# USB_Hub_Switch.net
KiCad netlist of a schematic drawn in EasyEDA Pro
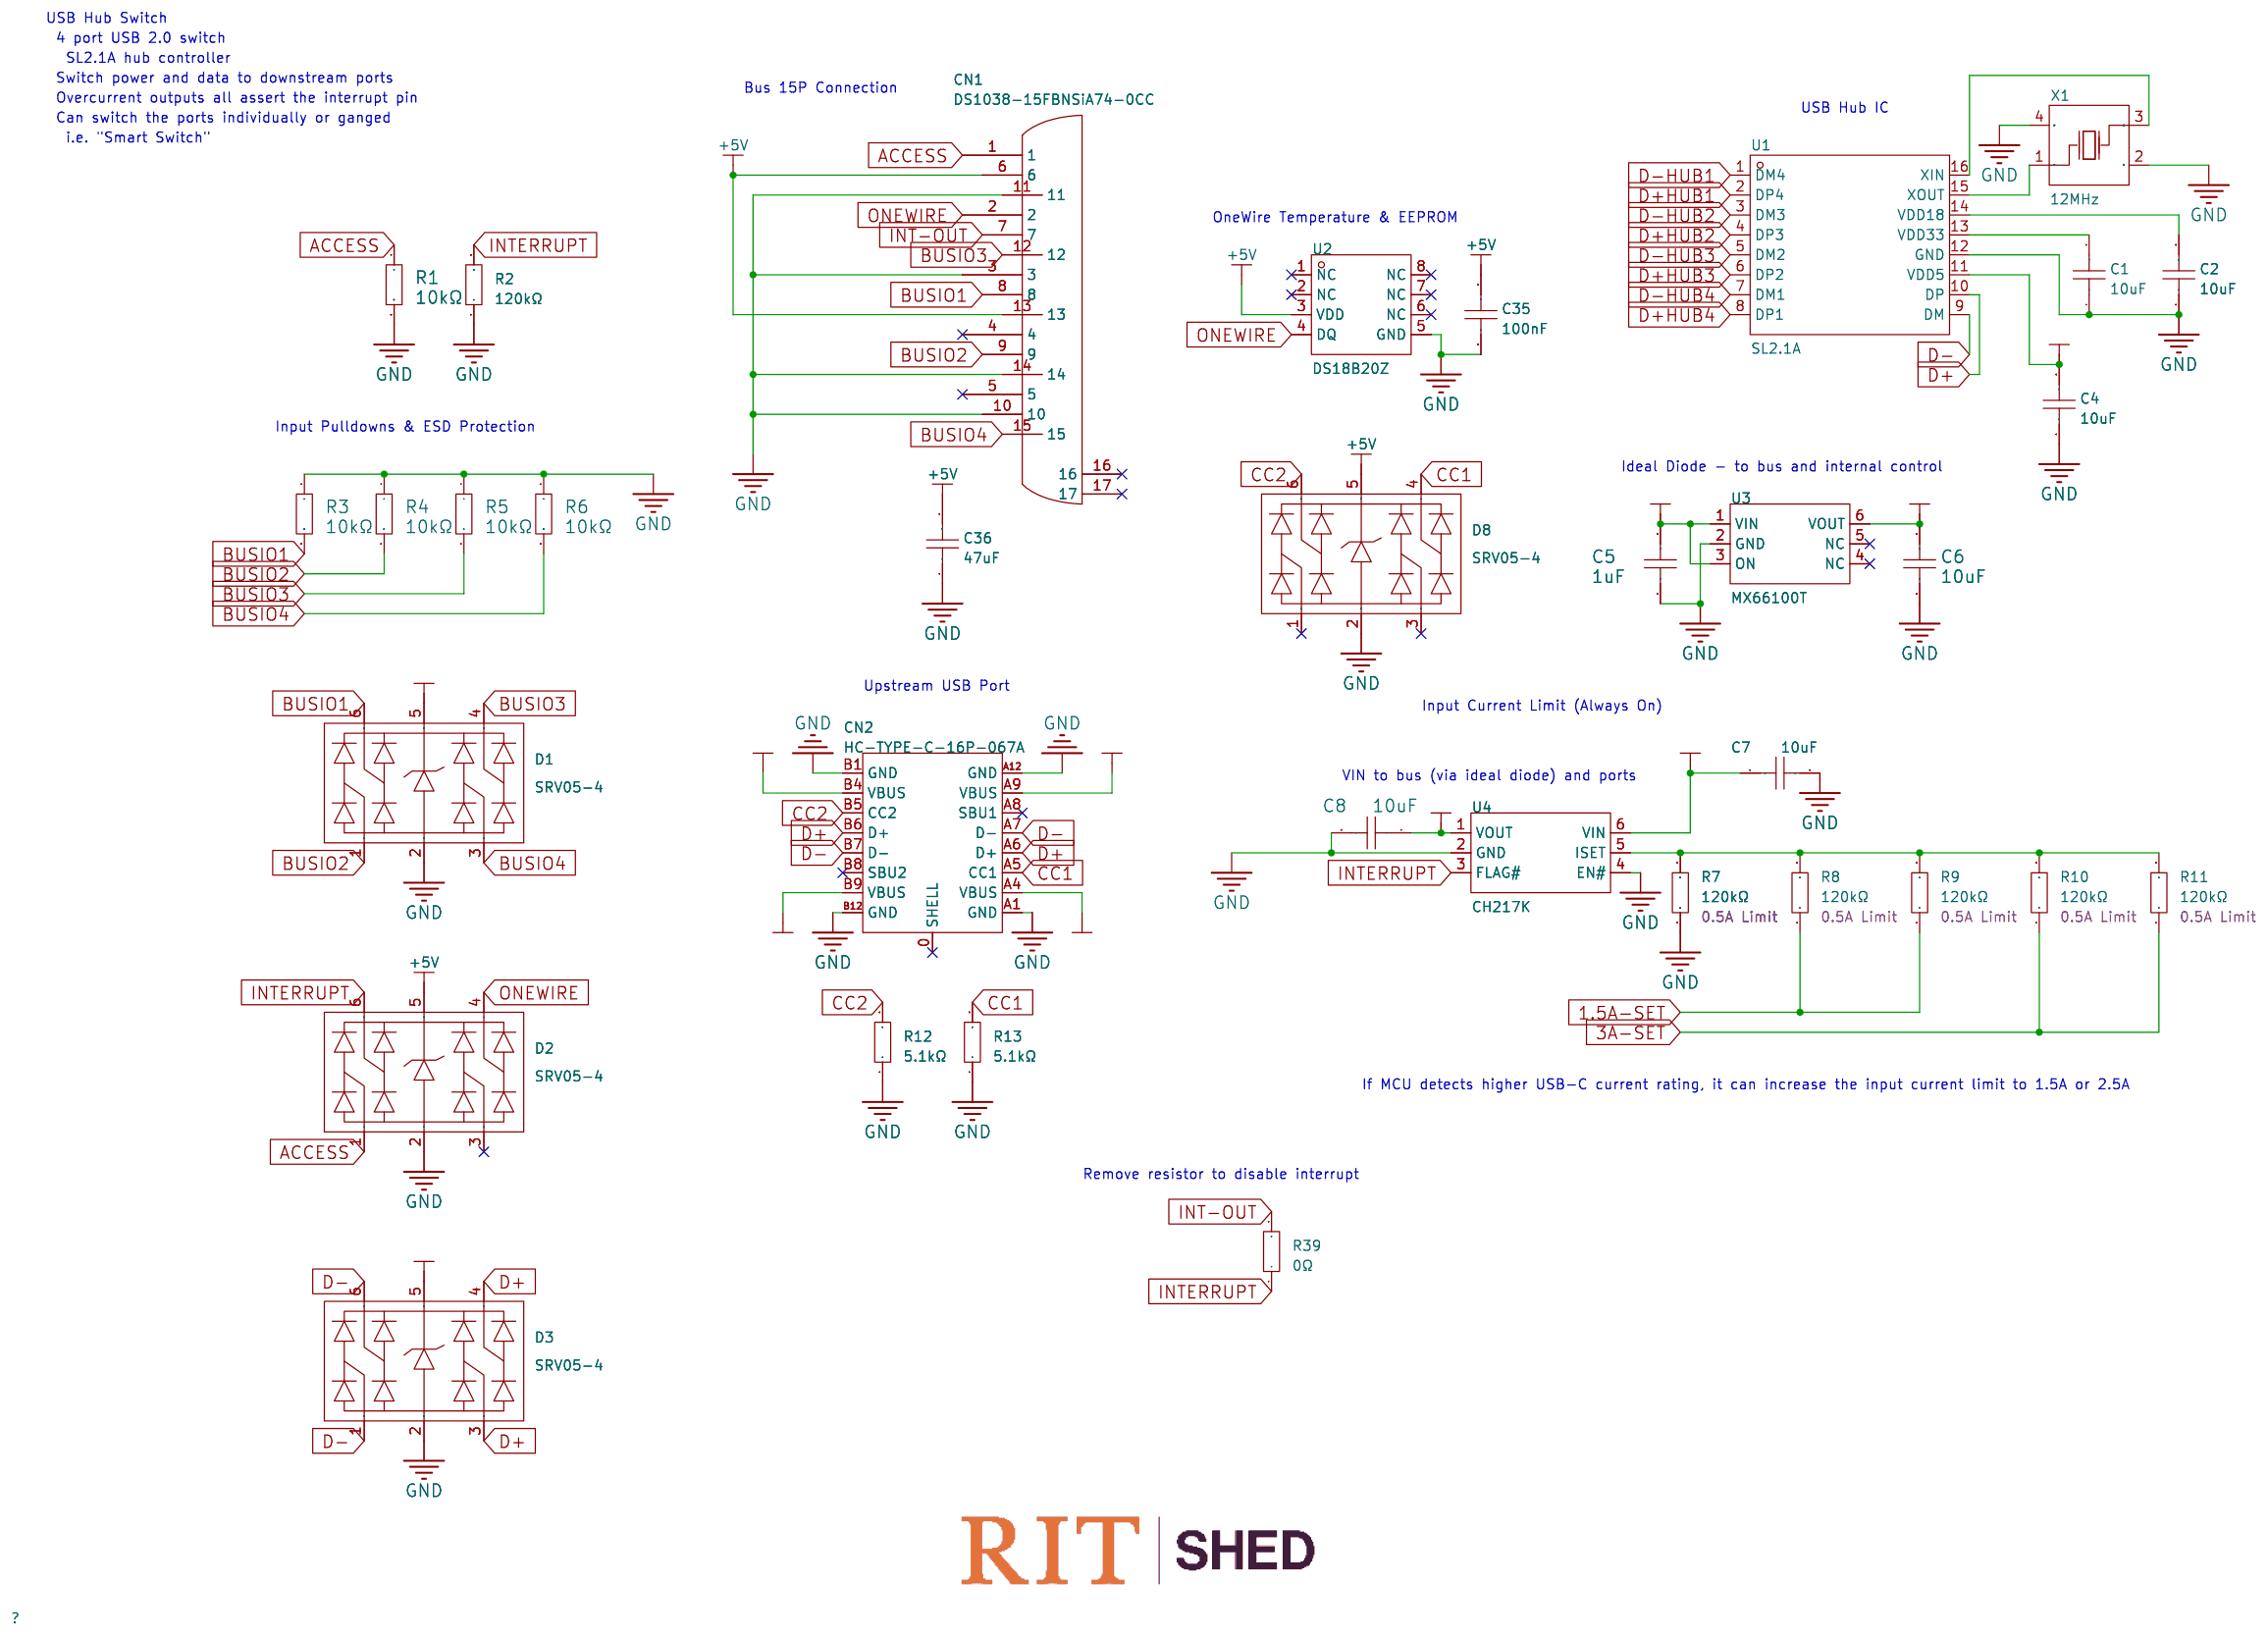
[diagram p0: Upstream Ports]
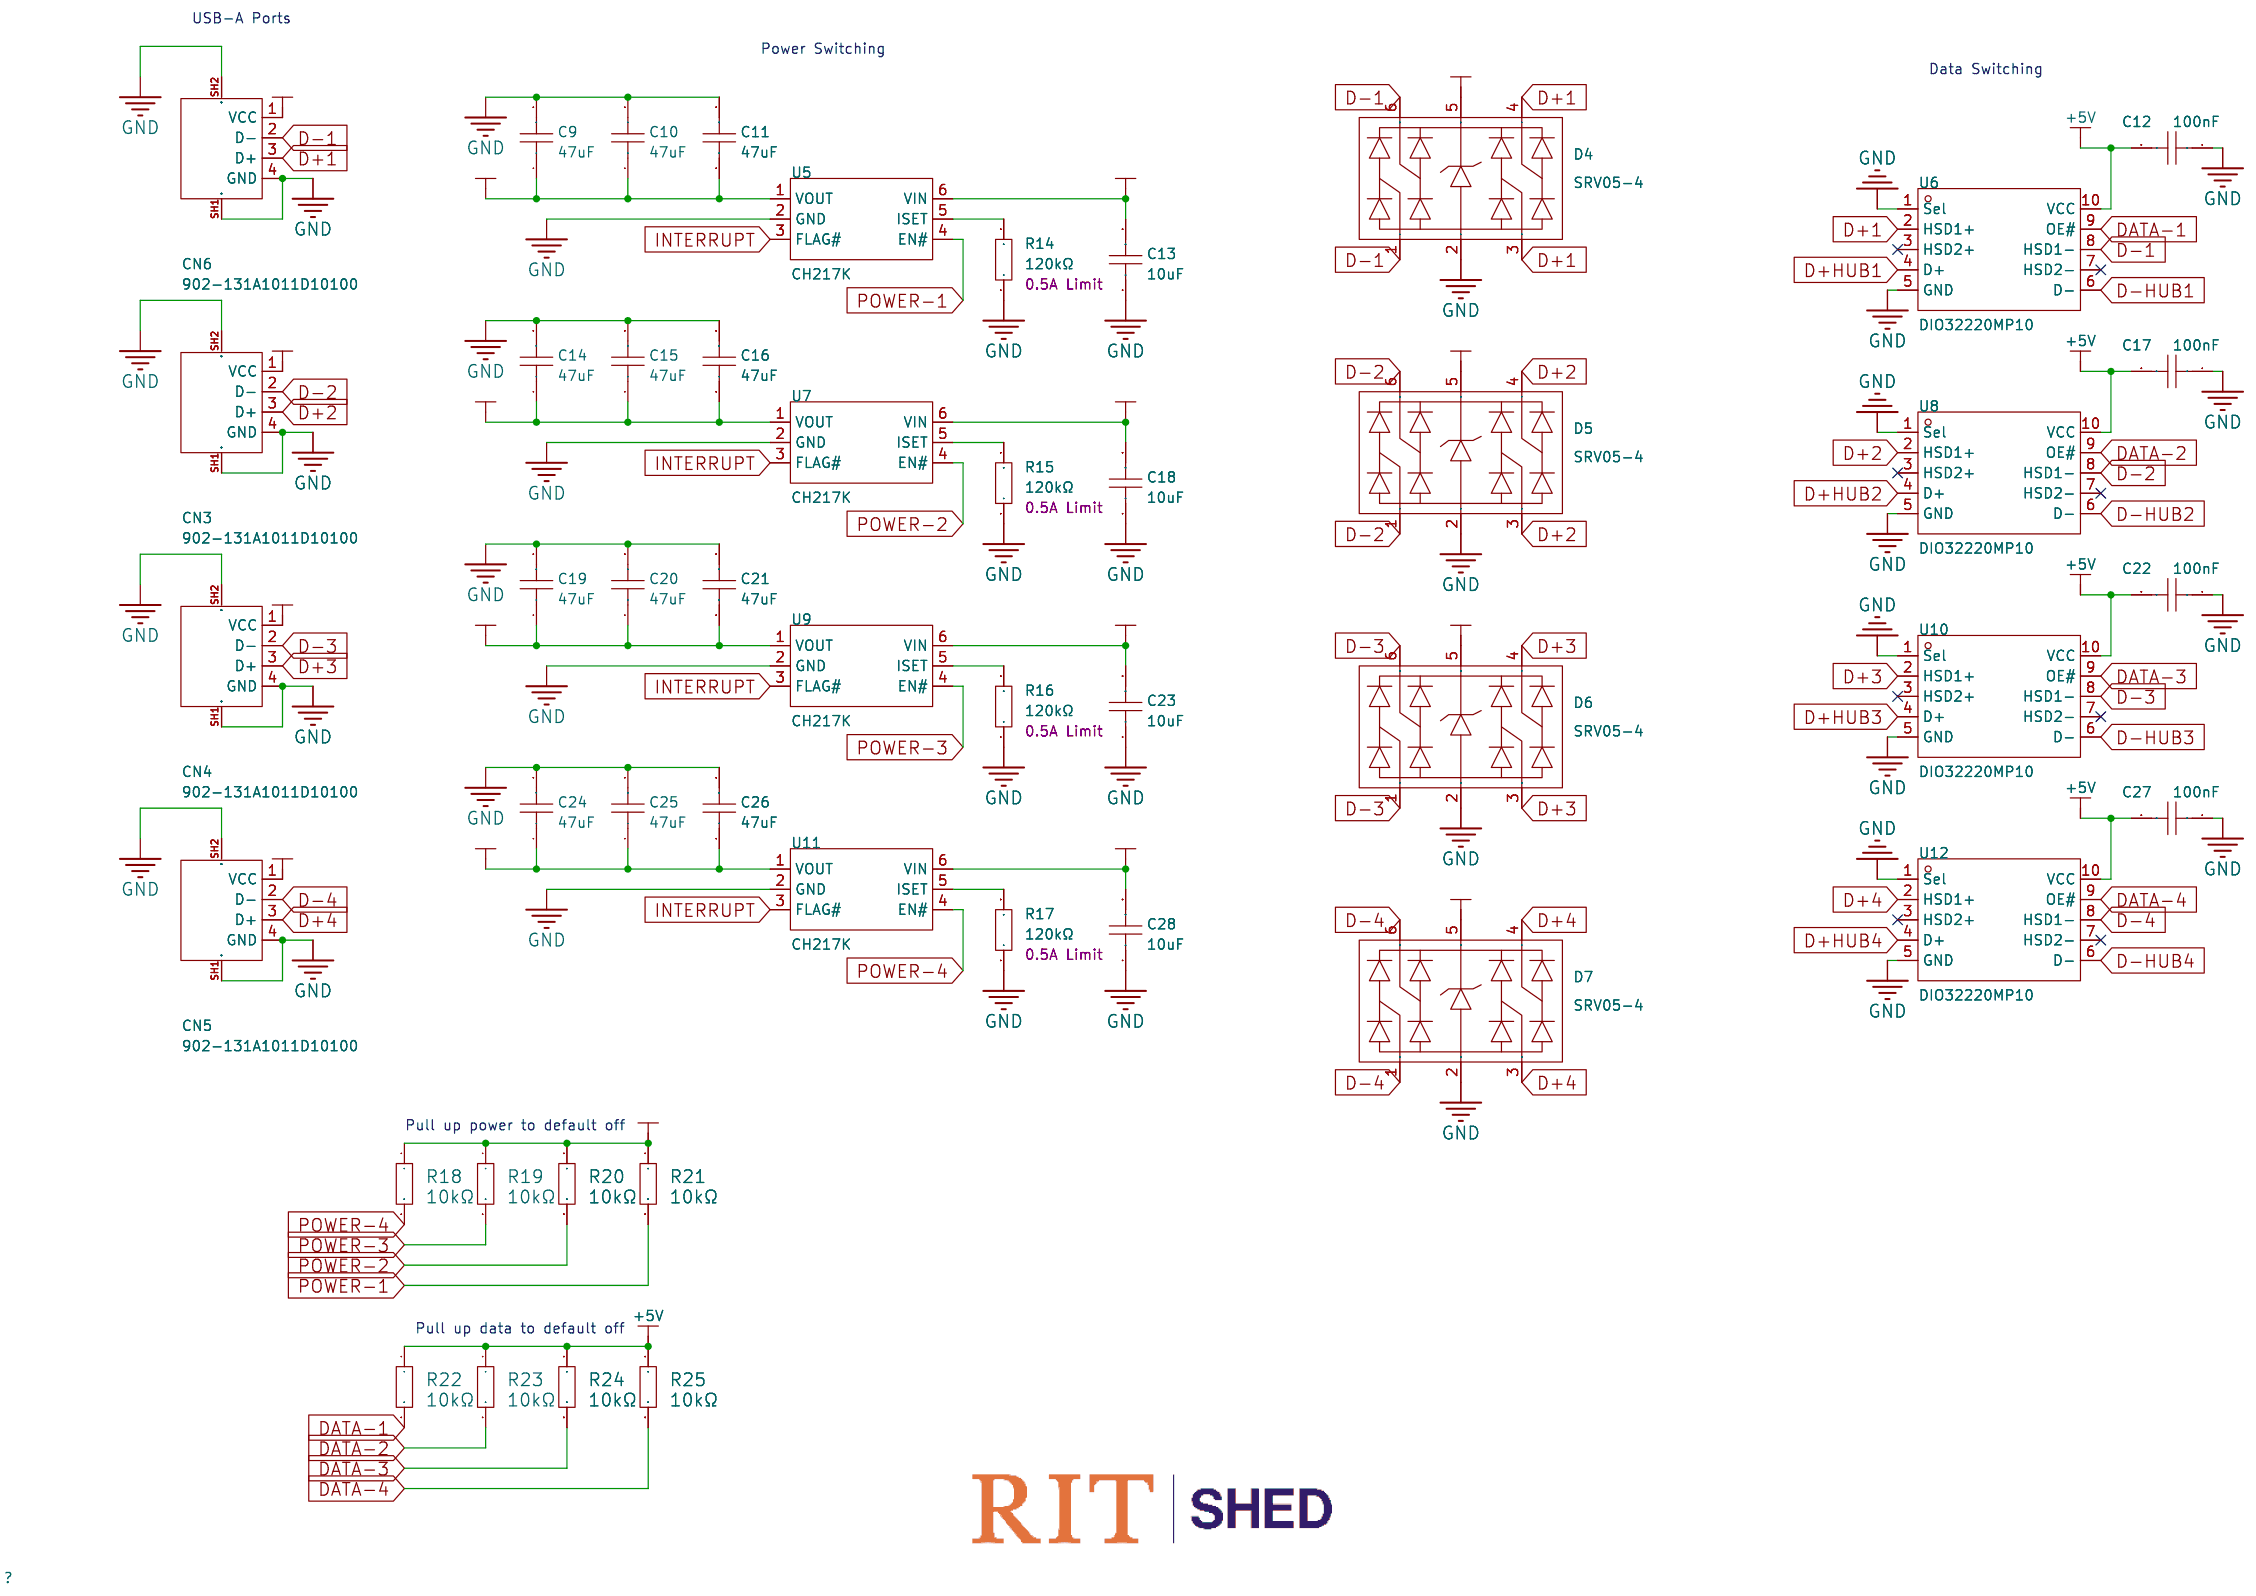
[diagram p1: Downstream Ports]
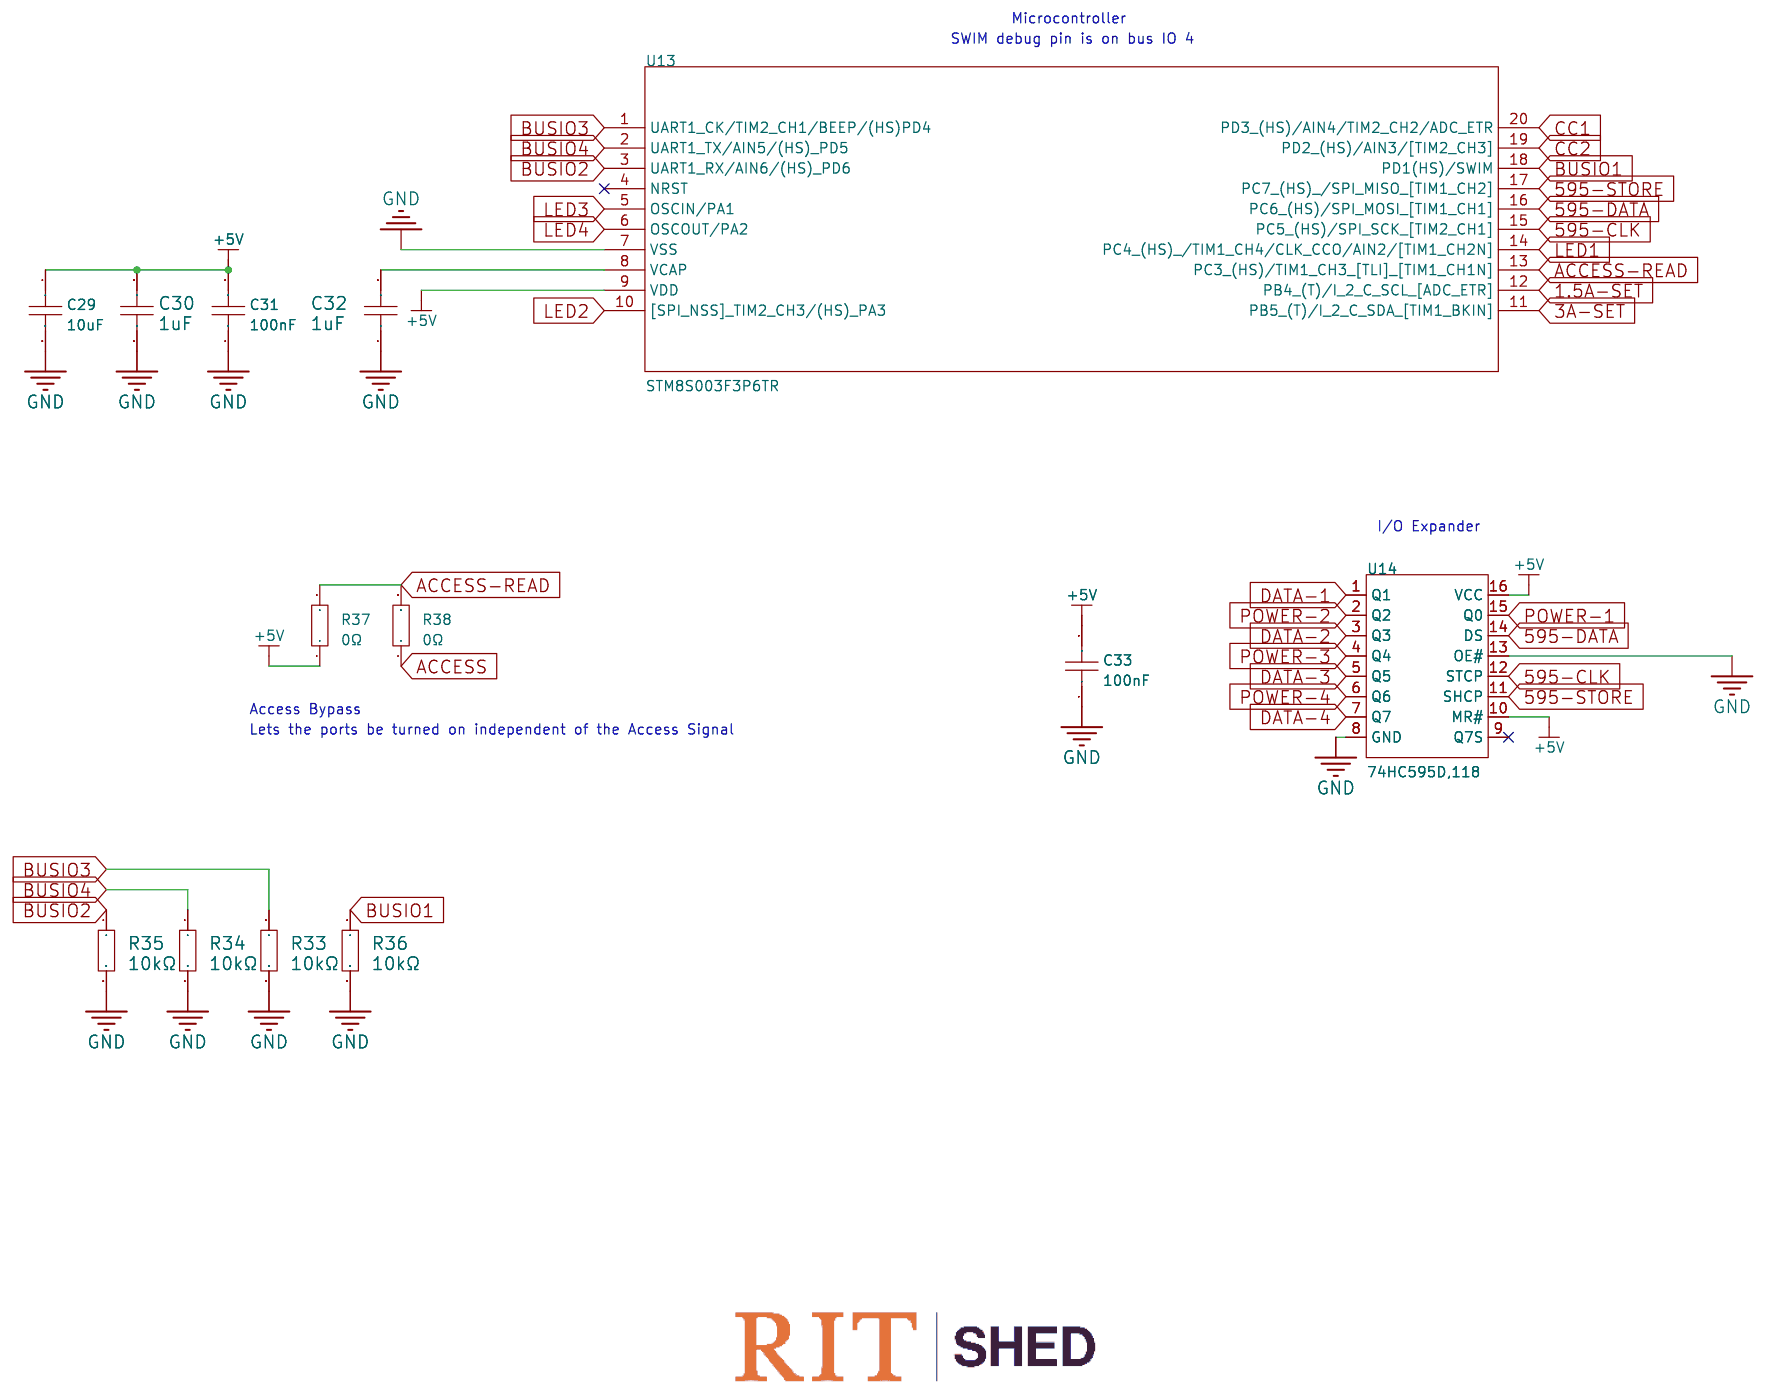
[diagram p2: Microcontroller]
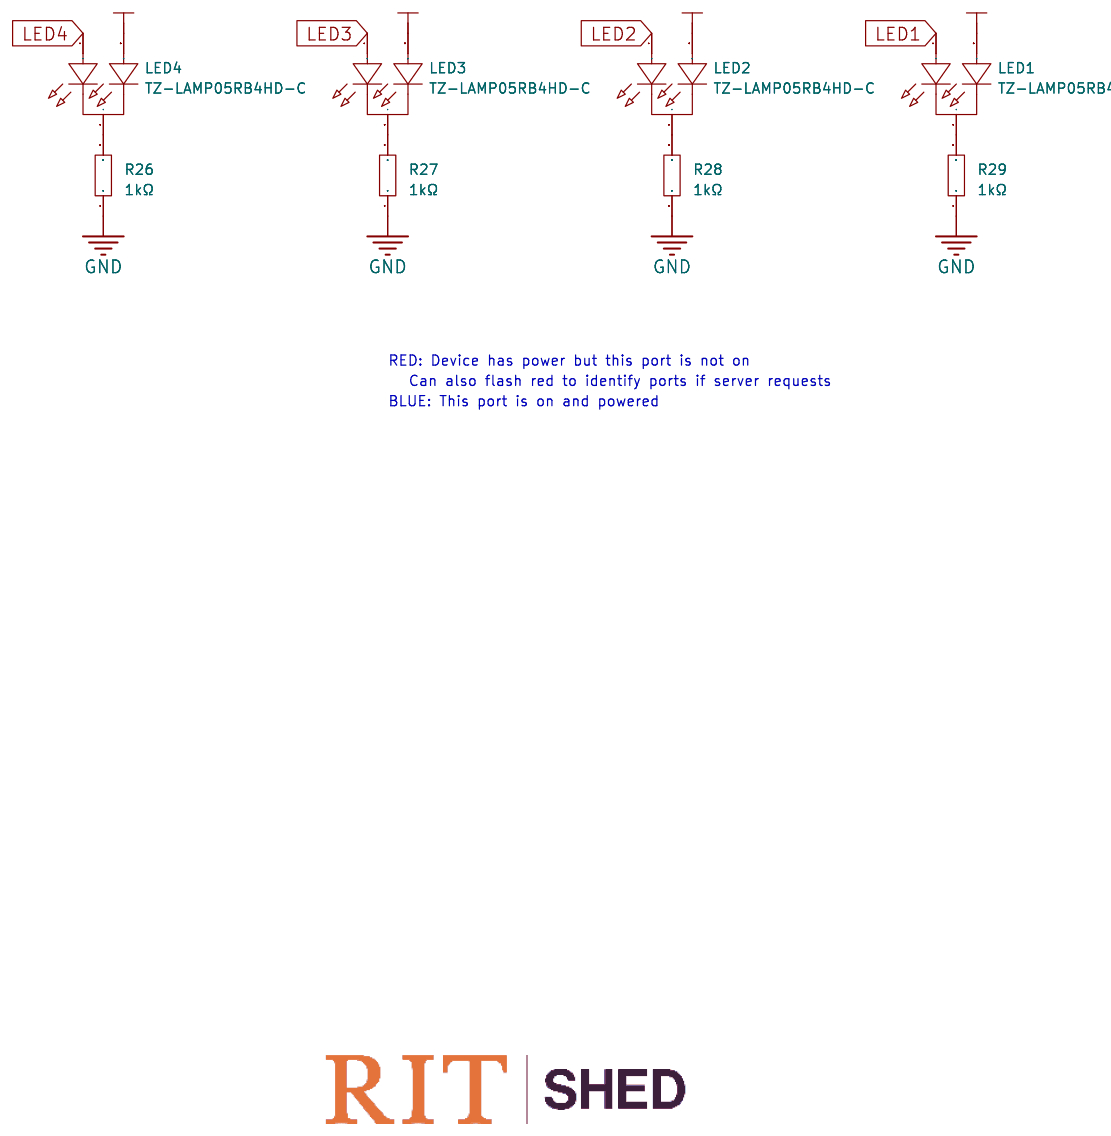
[diagram p3: Status LEDs]

(export (version "E")
  (design (tool "Eeschema 10.0.6"))
  (components
    (comp (ref "C1")
      (value "10uF")
      (footprint "easyedapro:C0603")
      (fields
        (field (name "Manufacturer Part") "CL10A106MA8NRNC")
        (field (name "Manufacturer") "SAMSUNG(三星)")
      )
      (libsource (lib "easyedapro") (part "CL10A106MA8NRNC"))
    )
    (comp (ref "C2")
      (value "10uF")
      (footprint "easyedapro:C0603")
      (fields
        (field (name "Manufacturer Part") "CL10A106MA8NRNC")
        (field (name "Manufacturer") "SAMSUNG(三星)")
      )
      (libsource (lib "easyedapro") (part "CL10A106MA8NRNC"))
    )
    (comp (ref "C4")
      (value "10uF")
      (footprint "easyedapro:C0603")
      (fields
        (field (name "Manufacturer Part") "CL10A106MA8NRNC")
        (field (name "Manufacturer") "SAMSUNG(三星)")
      )
      (libsource (lib "easyedapro") (part "CL10A106MA8NRNC"))
    )
    (comp (ref "C5")
      (value "1uF")
      (footprint "easyedapro:C0603")
      (fields
        (field (name "Manufacturer Part") "CL10A105KB8NNNC")
        (field (name "Manufacturer") "SAMSUNG(三星)")
      )
      (libsource (lib "easyedapro") (part "CL10A105KB8NNNC"))
    )
    (comp (ref "C6")
      (value "10uF")
      (footprint "easyedapro:C0603")
      (description "Capacitance:10uF Tolerance:±20% Tolerance:±20% Voltage Rating:25V Temperature Coefficient:X5R")
      (fields
        (field (name "Manufacturer Part") "CL10A106MA8NRNC")
        (field (name "Manufacturer") "SAMSUNG(三星)")
      )
      (libsource (lib "easyedapro") (part "CL10A106MA8NRNC"))
    )
    (comp (ref "C7")
      (value "10uF")
      (footprint "easyedapro:C0603")
      (fields
        (field (name "Manufacturer Part") "CL10A106MA8NRNC")
        (field (name "Manufacturer") "SAMSUNG(三星)")
      )
      (libsource (lib "easyedapro") (part "CL10A106MA8NRNC"))
    )
    (comp (ref "C8")
      (value "10uF")
      (footprint "easyedapro:C0603")
      (description "Capacitance:10uF Tolerance:±20% Tolerance:±20% Voltage Rating:25V Temperature Coefficient:X5R")
      (fields
        (field (name "Manufacturer Part") "CL10A106MA8NRNC")
        (field (name "Manufacturer") "SAMSUNG(三星)")
      )
      (libsource (lib "easyedapro") (part "CL10A106MA8NRNC"))
    )
    (comp (ref "C35")
      (value "100nF")
      (footprint "easyedapro:C0603")
      (description "Capacitance:100nF Tolerance:±10% Tolerance:±10% Voltage Rating:50V Temperature Coefficient:X7R")
      (fields
        (field (name "Manufacturer Part") "CC0603KRX7R9BB104")
        (field (name "Manufacturer") "YAGEO(国巨)")
      )
      (libsource (lib "easyedapro") (part "CC0603KRX7R9BB104"))
    )
    (comp (ref "C36")
      (value "47uF")
      (footprint "easyedapro:C1206")
      (description "Capacitance:47uF Tolerance:±20% Tolerance:±20% Voltage Rating:10V Temperature Coefficient:X5R")
      (fields
        (field (name "Manufacturer Part") "CL31A476MPHNNNE")
        (field (name "Manufacturer") "SAMSUNG(三星)")
      )
      (libsource (lib "easyedapro") (part "CL31A476MPHNNNE"))
    )
    (comp (ref "CN1")
      (value "DS1038-15FBNSiA74-0CC")
      (footprint "easyedapro:DSUB-TH_DS1038-15FBNSIA74-0CC")
      (fields (field (name "Manufacturer") "CONNFLY"))
      (libsource (lib "easyedapro") (part "DS1038-15FBNSIA74-0CC"))
    )
    (comp (ref "CN2")
      (value "HC-TYPE-C-16P-067A")
      (footprint "easyedapro:USB-SMD_HC-TYPE-C-16P-FLS7.2-5A-11")
      (fields (field (name "Manufacturer") "HC(虹成电子)"))
      (libsource (lib "easyedapro") (part "HC-TYPE-C-16P-067A"))
    )
    (comp (ref "D1")
      (value "SRV05-4")
      (footprint "easyedapro:SOT-23-6_L2.9-W1.6-P0.95-LS2.8-BL")
      (fields (field (name "Manufacturer") "TECH PUBLIC(台舟)"))
      (libsource (lib "easyedapro") (part "SRV05-4_C558418"))
    )
    (comp (ref "D2")
      (value "SRV05-4")
      (footprint "easyedapro:SOT-23-6_L2.9-W1.6-P0.95-LS2.8-BL")
      (fields (field (name "Manufacturer") "TECH PUBLIC(台舟)"))
      (libsource (lib "easyedapro") (part "SRV05-4_C558418"))
    )
    (comp (ref "D3")
      (value "SRV05-4")
      (footprint "easyedapro:SOT-23-6_L2.9-W1.6-P0.95-LS2.8-BL")
      (fields (field (name "Manufacturer") "TECH PUBLIC(台舟)"))
      (libsource (lib "easyedapro") (part "SRV05-4_C558418"))
    )
    (comp (ref "D8")
      (value "SRV05-4")
      (footprint "easyedapro:SOT-23-6_L2.9-W1.6-P0.95-LS2.8-BL")
      (fields (field (name "Manufacturer") "TECH PUBLIC(台舟)"))
      (libsource (lib "easyedapro") (part "SRV05-4_C558418"))
    )
    (comp (ref "R1")
      (value "10kΩ")
      (footprint "easyedapro:R0603")
      (fields
        (field (name "Manufacturer Part") "0603WAF1002T5E")
        (field (name "Manufacturer") "UNI-ROYAL(厚声)")
      )
      (libsource (lib "easyedapro") (part "0603WAF1002T5E"))
    )
    (comp (ref "R2")
      (value "120kΩ")
      (footprint "easyedapro:R0603")
      (fields
        (field (name "Manufacturer Part") "0603WAF1203T5E")
        (field (name "Manufacturer") "UNI-ROYAL(厚声)")
      )
      (libsource (lib "easyedapro") (part "0603WAF1203T5E"))
    )
    (comp (ref "R3")
      (value "10kΩ")
      (footprint "easyedapro:R0603")
      (fields
        (field (name "Manufacturer Part") "0603WAF1002T5E")
        (field (name "Manufacturer") "UNI-ROYAL(厚声)")
      )
      (libsource (lib "easyedapro") (part "0603WAF1002T5E"))
    )
    (comp (ref "R4")
      (value "10kΩ")
      (footprint "easyedapro:R0603")
      (fields
        (field (name "Manufacturer Part") "0603WAF1002T5E")
        (field (name "Manufacturer") "UNI-ROYAL(厚声)")
      )
      (libsource (lib "easyedapro") (part "0603WAF1002T5E"))
    )
    (comp (ref "R5")
      (value "10kΩ")
      (footprint "easyedapro:R0603")
      (fields
        (field (name "Manufacturer Part") "0603WAF1002T5E")
        (field (name "Manufacturer") "UNI-ROYAL(厚声)")
      )
      (libsource (lib "easyedapro") (part "0603WAF1002T5E"))
    )
    (comp (ref "R6")
      (value "10kΩ")
      (footprint "easyedapro:R0603")
      (fields
        (field (name "Manufacturer Part") "0603WAF1002T5E")
        (field (name "Manufacturer") "UNI-ROYAL(厚声)")
      )
      (libsource (lib "easyedapro") (part "0603WAF1002T5E"))
    )
    (comp (ref "R7")
      (value "120kΩ")
      (footprint "easyedapro:R0603")
      (fields
        (field (name "Manufacturer Part") "0603WAF1203T5E")
        (field (name "Manufacturer") "UNI-ROYAL(厚声)")
        (field (name "Note") "0.5A Limit")
      )
      (libsource (lib "easyedapro") (part "0603WAF1203T5E"))
    )
    (comp (ref "R8")
      (value "120kΩ")
      (footprint "easyedapro:R0603")
      (fields
        (field (name "Manufacturer Part") "0603WAF1203T5E")
        (field (name "Manufacturer") "UNI-ROYAL(厚声)")
        (field (name "Note") "0.5A Limit")
      )
      (libsource (lib "easyedapro") (part "0603WAF1203T5E"))
    )
    (comp (ref "R9")
      (value "120kΩ")
      (footprint "easyedapro:R0603")
      (fields
        (field (name "Manufacturer Part") "0603WAF1203T5E")
        (field (name "Manufacturer") "UNI-ROYAL(厚声)")
        (field (name "Note") "0.5A Limit")
      )
      (libsource (lib "easyedapro") (part "0603WAF1203T5E"))
    )
    (comp (ref "R10")
      (value "120kΩ")
      (footprint "easyedapro:R0603")
      (fields
        (field (name "Manufacturer Part") "0603WAF1203T5E")
        (field (name "Manufacturer") "UNI-ROYAL(厚声)")
        (field (name "Note") "0.5A Limit")
      )
      (libsource (lib "easyedapro") (part "0603WAF1203T5E"))
    )
    (comp (ref "R11")
      (value "120kΩ")
      (footprint "easyedapro:R0603")
      (fields
        (field (name "Manufacturer Part") "0603WAF1203T5E")
        (field (name "Manufacturer") "UNI-ROYAL(厚声)")
        (field (name "Note") "0.5A Limit")
      )
      (libsource (lib "easyedapro") (part "0603WAF1203T5E"))
    )
    (comp (ref "R12")
      (value "5.1kΩ")
      (footprint "easyedapro:R0603")
      (fields
        (field (name "Manufacturer Part") "0603WAF5101T5E")
        (field (name "Manufacturer") "UNI-ROYAL(厚声)")
      )
      (libsource (lib "easyedapro") (part "0603WAF5101T5E"))
    )
    (comp (ref "R13")
      (value "5.1kΩ")
      (footprint "easyedapro:R0603")
      (fields
        (field (name "Manufacturer Part") "0603WAF5101T5E")
        (field (name "Manufacturer") "UNI-ROYAL(厚声)")
      )
      (libsource (lib "easyedapro") (part "0603WAF5101T5E"))
    )
    (comp (ref "R39")
      (value "0Ω")
      (footprint "easyedapro:R0805")
      (fields
        (field (name "Manufacturer Part") "0805W8F0000T5E")
        (field (name "Manufacturer") "UNI-ROYAL(厚声)")
      )
      (libsource (lib "easyedapro") (part "0805W8F0000T5E"))
    )
    (comp (ref "U1")
      (value "SL2.1A")
      (footprint "easyedapro:SOP-16_L10.0-W3.9-P1.27-LS6.0-BL")
      (fields (field (name "Manufacturer") "CoreChips(和芯润德)"))
      (libsource (lib "easyedapro") (part "SL2.1A"))
    )
    (comp (ref "U2")
      (value "DS18B20Z")
      (footprint "easyedapro:SOP-8_L4.9-W3.9-P1.27-LS6.0-BL")
      (description "Resolution:±0.4°C Resolution:±0.4°C Supply Voltage:2.5V~5.5V Supply Voltage:2.5V~5.5V")
      (fields (field (name "Manufacturer") "UMW(友台半导体)"))
      (libsource (lib "easyedapro") (part "DS18B20Z"))
    )
    (comp (ref "U3")
      (value "MX66100T")
      (footprint "easyedapro:SOT-23-6_L2.9-W1.6-P0.95-LS2.9-BL")
      (fields (field (name "Manufacturer") "Wuxi Maxinmicro(无锡明芯微)"))
      (libsource (lib "easyedapro") (part "MX66100T"))
    )
    (comp (ref "U4")
      (value "CH217K")
      (footprint "easyedapro:SOT-23-6_L2.9-W1.6-P0.95-LS2.8-BL")
      (fields (field (name "Manufacturer") "WCH(南京沁恒)"))
      (libsource (lib "easyedapro") (part "CH217K"))
    )
    (comp (ref "X1")
      (value "12MHz")
      (footprint "easyedapro:OSC-SMD_4P-L3.2-W2.5-BL")
      (fields (field (name "Manufacturer Part") "X322512MSB4SI") (field (name "Manufacturer") "YXC(扬兴晶振)"))
      (libsource (lib "easyedapro") (part "X322512MSB4SI"))
    )
    (comp (ref "C9")
      (value "47uF")
      (footprint "easyedapro:C1206")
      (description "Capacitance:47uF Tolerance:±20% Tolerance:±20% Voltage Rating:10V Temperature Coefficient:X5R")
      (fields
        (field (name "Manufacturer Part") "CL31A476MPHNNNE")
        (field (name "Manufacturer") "SAMSUNG(三星)")
      )
      (libsource (lib "easyedapro") (part "CL31A476MPHNNNE"))
    )
    (comp (ref "C10")
      (value "47uF")
      (footprint "easyedapro:C1206")
      (description "Capacitance:47uF Tolerance:±20% Tolerance:±20% Voltage Rating:10V Temperature Coefficient:X5R")
      (fields
        (field (name "Manufacturer Part") "CL31A476MPHNNNE")
        (field (name "Manufacturer") "SAMSUNG(三星)")
      )
      (libsource (lib "easyedapro") (part "CL31A476MPHNNNE"))
    )
    (comp (ref "C11")
      (value "47uF")
      (footprint "easyedapro:C1206")
      (description "Capacitance:47uF Tolerance:±20% Tolerance:±20% Voltage Rating:10V Temperature Coefficient:X5R")
      (fields
        (field (name "Manufacturer Part") "CL31A476MPHNNNE")
        (field (name "Manufacturer") "SAMSUNG(三星)")
      )
      (libsource (lib "easyedapro") (part "CL31A476MPHNNNE"))
    )
    (comp (ref "C12")
      (value "100nF")
      (footprint "easyedapro:C0603")
      (description "Capacitance:100nF Tolerance:±10% Tolerance:±10% Voltage Rating:50V Temperature Coefficient:X7R")
      (fields
        (field (name "Manufacturer Part") "CC0603KRX7R9BB104")
        (field (name "Manufacturer") "YAGEO(国巨)")
      )
      (libsource (lib "easyedapro") (part "CC0603KRX7R9BB104"))
    )
    (comp (ref "C13")
      (value "10uF")
      (footprint "easyedapro:C0603")
      (fields
        (field (name "Manufacturer Part") "CL10A106MA8NRNC")
        (field (name "Manufacturer") "SAMSUNG(三星)")
      )
      (libsource (lib "easyedapro") (part "CL10A106MA8NRNC"))
    )
    (comp (ref "C14")
      (value "47uF")
      (footprint "easyedapro:C1206")
      (description "Capacitance:47uF Tolerance:±20% Tolerance:±20% Voltage Rating:10V Temperature Coefficient:X5R")
      (fields
        (field (name "Manufacturer Part") "CL31A476MPHNNNE")
        (field (name "Manufacturer") "SAMSUNG(三星)")
      )
      (libsource (lib "easyedapro") (part "CL31A476MPHNNNE"))
    )
    (comp (ref "C15")
      (value "47uF")
      (footprint "easyedapro:C1206")
      (description "Capacitance:47uF Tolerance:±20% Tolerance:±20% Voltage Rating:10V Temperature Coefficient:X5R")
      (fields
        (field (name "Manufacturer Part") "CL31A476MPHNNNE")
        (field (name "Manufacturer") "SAMSUNG(三星)")
      )
      (libsource (lib "easyedapro") (part "CL31A476MPHNNNE"))
    )
    (comp (ref "C16")
      (value "47uF")
      (footprint "easyedapro:C1206")
      (description "Capacitance:47uF Tolerance:±20% Tolerance:±20% Voltage Rating:10V Temperature Coefficient:X5R")
      (fields
        (field (name "Manufacturer Part") "CL31A476MPHNNNE")
        (field (name "Manufacturer") "SAMSUNG(三星)")
      )
      (libsource (lib "easyedapro") (part "CL31A476MPHNNNE"))
    )
    (comp (ref "C17")
      (value "100nF")
      (footprint "easyedapro:C0603")
      (description "Capacitance:100nF Tolerance:±10% Tolerance:±10% Voltage Rating:50V Temperature Coefficient:X7R")
      (fields
        (field (name "Manufacturer Part") "CC0603KRX7R9BB104")
        (field (name "Manufacturer") "YAGEO(国巨)")
      )
      (libsource (lib "easyedapro") (part "CC0603KRX7R9BB104"))
    )
    (comp (ref "C18")
      (value "10uF")
      (footprint "easyedapro:C0603")
      (fields
        (field (name "Manufacturer Part") "CL10A106MA8NRNC")
        (field (name "Manufacturer") "SAMSUNG(三星)")
      )
      (libsource (lib "easyedapro") (part "CL10A106MA8NRNC"))
    )
    (comp (ref "C19")
      (value "47uF")
      (footprint "easyedapro:C1206")
      (description "Capacitance:47uF Tolerance:±20% Tolerance:±20% Voltage Rating:10V Temperature Coefficient:X5R")
      (fields
        (field (name "Manufacturer Part") "CL31A476MPHNNNE")
        (field (name "Manufacturer") "SAMSUNG(三星)")
      )
      (libsource (lib "easyedapro") (part "CL31A476MPHNNNE"))
    )
    (comp (ref "C20")
      (value "47uF")
      (footprint "easyedapro:C1206")
      (description "Capacitance:47uF Tolerance:±20% Tolerance:±20% Voltage Rating:10V Temperature Coefficient:X5R")
      (fields
        (field (name "Manufacturer Part") "CL31A476MPHNNNE")
        (field (name "Manufacturer") "SAMSUNG(三星)")
      )
      (libsource (lib "easyedapro") (part "CL31A476MPHNNNE"))
    )
    (comp (ref "C21")
      (value "47uF")
      (footprint "easyedapro:C1206")
      (description "Capacitance:47uF Tolerance:±20% Tolerance:±20% Voltage Rating:10V Temperature Coefficient:X5R")
      (fields
        (field (name "Manufacturer Part") "CL31A476MPHNNNE")
        (field (name "Manufacturer") "SAMSUNG(三星)")
      )
      (libsource (lib "easyedapro") (part "CL31A476MPHNNNE"))
    )
    (comp (ref "C22")
      (value "100nF")
      (footprint "easyedapro:C0603")
      (description "Capacitance:100nF Tolerance:±10% Tolerance:±10% Voltage Rating:50V Temperature Coefficient:X7R")
      (fields
        (field (name "Manufacturer Part") "CC0603KRX7R9BB104")
        (field (name "Manufacturer") "YAGEO(国巨)")
      )
      (libsource (lib "easyedapro") (part "CC0603KRX7R9BB104"))
    )
    (comp (ref "C23")
      (value "10uF")
      (footprint "easyedapro:C0603")
      (fields
        (field (name "Manufacturer Part") "CL10A106MA8NRNC")
        (field (name "Manufacturer") "SAMSUNG(三星)")
      )
      (libsource (lib "easyedapro") (part "CL10A106MA8NRNC"))
    )
    (comp (ref "C24")
      (value "47uF")
      (footprint "easyedapro:C1206")
      (description "Capacitance:47uF Tolerance:±20% Tolerance:±20% Voltage Rating:10V Temperature Coefficient:X5R")
      (fields
        (field (name "Manufacturer Part") "CL31A476MPHNNNE")
        (field (name "Manufacturer") "SAMSUNG(三星)")
      )
      (libsource (lib "easyedapro") (part "CL31A476MPHNNNE"))
    )
    (comp (ref "C25")
      (value "47uF")
      (footprint "easyedapro:C1206")
      (description "Capacitance:47uF Tolerance:±20% Tolerance:±20% Voltage Rating:10V Temperature Coefficient:X5R")
      (fields
        (field (name "Manufacturer Part") "CL31A476MPHNNNE")
        (field (name "Manufacturer") "SAMSUNG(三星)")
      )
      (libsource (lib "easyedapro") (part "CL31A476MPHNNNE"))
    )
    (comp (ref "C26")
      (value "47uF")
      (footprint "easyedapro:C1206")
      (description "Capacitance:47uF Tolerance:±20% Tolerance:±20% Voltage Rating:10V Temperature Coefficient:X5R")
      (fields
        (field (name "Manufacturer Part") "CL31A476MPHNNNE")
        (field (name "Manufacturer") "SAMSUNG(三星)")
      )
      (libsource (lib "easyedapro") (part "CL31A476MPHNNNE"))
    )
    (comp (ref "C27")
      (value "100nF")
      (footprint "easyedapro:C0603")
      (description "Capacitance:100nF Tolerance:±10% Tolerance:±10% Voltage Rating:50V Temperature Coefficient:X7R")
      (fields
        (field (name "Manufacturer Part") "CC0603KRX7R9BB104")
        (field (name "Manufacturer") "YAGEO(国巨)")
      )
      (libsource (lib "easyedapro") (part "CC0603KRX7R9BB104"))
    )
    (comp (ref "C28")
      (value "10uF")
      (footprint "easyedapro:C0603")
      (fields
        (field (name "Manufacturer Part") "CL10A106MA8NRNC")
        (field (name "Manufacturer") "SAMSUNG(三星)")
      )
      (libsource (lib "easyedapro") (part "CL10A106MA8NRNC"))
    )
    (comp (ref "CN3")
      (value "902-131A1011D10100")
      (footprint "easyedapro:USB-A-TH__USB-AF-90")
      (fields (field (name "Manufacturer") "精拓金"))
      (libsource (lib "easyedapro") (part "JTJ-USB-AF-08"))
    )
    (comp (ref "CN4")
      (value "902-131A1011D10100")
      (footprint "easyedapro:USB-A-TH__USB-AF-90")
      (fields (field (name "Manufacturer") "精拓金"))
      (libsource (lib "easyedapro") (part "JTJ-USB-AF-08"))
    )
    (comp (ref "CN5")
      (value "902-131A1011D10100")
      (footprint "easyedapro:USB-A-TH__USB-AF-90")
      (fields (field (name "Manufacturer") "精拓金"))
      (libsource (lib "easyedapro") (part "JTJ-USB-AF-08"))
    )
    (comp (ref "CN6")
      (value "902-131A1011D10100")
      (footprint "easyedapro:USB-A-TH__USB-AF-90")
      (fields (field (name "Manufacturer") "精拓金"))
      (libsource (lib "easyedapro") (part "JTJ-USB-AF-08"))
    )
    (comp (ref "D4")
      (value "SRV05-4")
      (footprint "easyedapro:SOT-23-6_L2.9-W1.6-P0.95-LS2.8-BL")
      (fields (field (name "Manufacturer") "TECH PUBLIC(台舟)"))
      (libsource (lib "easyedapro") (part "SRV05-4_C558418"))
    )
    (comp (ref "D5")
      (value "SRV05-4")
      (footprint "easyedapro:SOT-23-6_L2.9-W1.6-P0.95-LS2.8-BL")
      (fields (field (name "Manufacturer") "TECH PUBLIC(台舟)"))
      (libsource (lib "easyedapro") (part "SRV05-4_C558418"))
    )
    (comp (ref "D6")
      (value "SRV05-4")
      (footprint "easyedapro:SOT-23-6_L2.9-W1.6-P0.95-LS2.8-BL")
      (fields (field (name "Manufacturer") "TECH PUBLIC(台舟)"))
      (libsource (lib "easyedapro") (part "SRV05-4_C558418"))
    )
    (comp (ref "D7")
      (value "SRV05-4")
      (footprint "easyedapro:SOT-23-6_L2.9-W1.6-P0.95-LS2.8-BL")
      (fields (field (name "Manufacturer") "TECH PUBLIC(台舟)"))
      (libsource (lib "easyedapro") (part "SRV05-4_C558418"))
    )
    (comp (ref "R14")
      (value "120kΩ")
      (footprint "easyedapro:R0603")
      (fields
        (field (name "Manufacturer Part") "0603WAF1203T5E")
        (field (name "Manufacturer") "UNI-ROYAL(厚声)")
        (field (name "Note") "0.5A Limit")
      )
      (libsource (lib "easyedapro") (part "0603WAF1203T5E"))
    )
    (comp (ref "R15")
      (value "120kΩ")
      (footprint "easyedapro:R0603")
      (fields
        (field (name "Manufacturer Part") "0603WAF1203T5E")
        (field (name "Manufacturer") "UNI-ROYAL(厚声)")
        (field (name "Note") "0.5A Limit")
      )
      (libsource (lib "easyedapro") (part "0603WAF1203T5E"))
    )
    (comp (ref "R16")
      (value "120kΩ")
      (footprint "easyedapro:R0603")
      (fields
        (field (name "Manufacturer Part") "0603WAF1203T5E")
        (field (name "Manufacturer") "UNI-ROYAL(厚声)")
        (field (name "Note") "0.5A Limit")
      )
      (libsource (lib "easyedapro") (part "0603WAF1203T5E"))
    )
    (comp (ref "R17")
      (value "120kΩ")
      (footprint "easyedapro:R0603")
      (fields
        (field (name "Manufacturer Part") "0603WAF1203T5E")
        (field (name "Manufacturer") "UNI-ROYAL(厚声)")
        (field (name "Note") "0.5A Limit")
      )
      (libsource (lib "easyedapro") (part "0603WAF1203T5E"))
    )
    (comp (ref "R18")
      (value "10kΩ")
      (footprint "easyedapro:R0603")
      (fields
        (field (name "Manufacturer Part") "0603WAF1002T5E")
        (field (name "Manufacturer") "UNI-ROYAL(厚声)")
      )
      (libsource (lib "easyedapro") (part "0603WAF1002T5E"))
    )
    (comp (ref "R19")
      (value "10kΩ")
      (footprint "easyedapro:R0603")
      (fields
        (field (name "Manufacturer Part") "0603WAF1002T5E")
        (field (name "Manufacturer") "UNI-ROYAL(厚声)")
      )
      (libsource (lib "easyedapro") (part "0603WAF1002T5E"))
    )
    (comp (ref "R20")
      (value "10kΩ")
      (footprint "easyedapro:R0603")
      (fields
        (field (name "Manufacturer Part") "0603WAF1002T5E")
        (field (name "Manufacturer") "UNI-ROYAL(厚声)")
      )
      (libsource (lib "easyedapro") (part "0603WAF1002T5E"))
    )
    (comp (ref "R21")
      (value "10kΩ")
      (footprint "easyedapro:R0603")
      (fields
        (field (name "Manufacturer Part") "0603WAF1002T5E")
        (field (name "Manufacturer") "UNI-ROYAL(厚声)")
      )
      (libsource (lib "easyedapro") (part "0603WAF1002T5E"))
    )
    (comp (ref "R22")
      (value "10kΩ")
      (footprint "easyedapro:R0603")
      (fields
        (field (name "Manufacturer Part") "0603WAF1002T5E")
        (field (name "Manufacturer") "UNI-ROYAL(厚声)")
      )
      (libsource (lib "easyedapro") (part "0603WAF1002T5E"))
    )
    (comp (ref "R23")
      (value "10kΩ")
      (footprint "easyedapro:R0603")
      (fields
        (field (name "Manufacturer Part") "0603WAF1002T5E")
        (field (name "Manufacturer") "UNI-ROYAL(厚声)")
      )
      (libsource (lib "easyedapro") (part "0603WAF1002T5E"))
    )
    (comp (ref "R24")
      (value "10kΩ")
      (footprint "easyedapro:R0603")
      (fields
        (field (name "Manufacturer Part") "0603WAF1002T5E")
        (field (name "Manufacturer") "UNI-ROYAL(厚声)")
      )
      (libsource (lib "easyedapro") (part "0603WAF1002T5E"))
    )
    (comp (ref "R25")
      (value "10kΩ")
      (footprint "easyedapro:R0603")
      (fields
        (field (name "Manufacturer Part") "0603WAF1002T5E")
        (field (name "Manufacturer") "UNI-ROYAL(厚声)")
      )
      (libsource (lib "easyedapro") (part "0603WAF1002T5E"))
    )
    (comp (ref "U5")
      (value "CH217K")
      (footprint "easyedapro:SOT-23-6_L2.9-W1.6-P0.95-LS2.8-BL")
      (fields (field (name "Manufacturer") "WCH(南京沁恒)"))
      (libsource (lib "easyedapro") (part "CH217K"))
    )
    (comp (ref "U6")
      (value "DIO32220MP10")
      (footprint "easyedapro:MSOP-10_L3.0-W3.0-P0.50-LS5.0-BL")
      (fields (field (name "Manufacturer") "DIOO(帝奥微)"))
      (libsource (lib "easyedapro") (part "DIO32220MP10"))
    )
    (comp (ref "U7")
      (value "CH217K")
      (footprint "easyedapro:SOT-23-6_L2.9-W1.6-P0.95-LS2.8-BL")
      (fields (field (name "Manufacturer") "WCH(南京沁恒)"))
      (libsource (lib "easyedapro") (part "CH217K"))
    )
    (comp (ref "U8")
      (value "DIO32220MP10")
      (footprint "easyedapro:MSOP-10_L3.0-W3.0-P0.50-LS5.0-BL")
      (fields (field (name "Manufacturer") "DIOO(帝奥微)"))
      (libsource (lib "easyedapro") (part "DIO32220MP10"))
    )
    (comp (ref "U9")
      (value "CH217K")
      (footprint "easyedapro:SOT-23-6_L2.9-W1.6-P0.95-LS2.8-BL")
      (fields (field (name "Manufacturer") "WCH(南京沁恒)"))
      (libsource (lib "easyedapro") (part "CH217K"))
    )
    (comp (ref "U10")
      (value "DIO32220MP10")
      (footprint "easyedapro:MSOP-10_L3.0-W3.0-P0.50-LS5.0-BL")
      (fields (field (name "Manufacturer") "DIOO(帝奥微)"))
      (libsource (lib "easyedapro") (part "DIO32220MP10"))
    )
    (comp (ref "U11")
      (value "CH217K")
      (footprint "easyedapro:SOT-23-6_L2.9-W1.6-P0.95-LS2.8-BL")
      (fields (field (name "Manufacturer") "WCH(南京沁恒)"))
      (libsource (lib "easyedapro") (part "CH217K"))
    )
    (comp (ref "U12")
      (value "DIO32220MP10")
      (footprint "easyedapro:MSOP-10_L3.0-W3.0-P0.50-LS5.0-BL")
      (fields (field (name "Manufacturer") "DIOO(帝奥微)"))
      (libsource (lib "easyedapro") (part "DIO32220MP10"))
    )
    (comp (ref "C29")
      (value "10uF")
      (footprint "easyedapro:C0603")
      (fields
        (field (name "Manufacturer Part") "CL10A106MA8NRNC")
        (field (name "Manufacturer") "SAMSUNG(三星)")
      )
      (libsource (lib "easyedapro") (part "CL10A106MA8NRNC"))
    )
    (comp (ref "C30")
      (value "1uF")
      (footprint "easyedapro:C0603")
      (fields
        (field (name "Manufacturer Part") "CL10A105KB8NNNC")
        (field (name "Manufacturer") "SAMSUNG(三星)")
      )
      (libsource (lib "easyedapro") (part "CL10A105KB8NNNC"))
    )
    (comp (ref "C31")
      (value "100nF")
      (footprint "easyedapro:C0603")
      (description "Capacitance:100nF Tolerance:±10% Tolerance:±10% Voltage Rating:50V Temperature Coefficient:X7R")
      (fields
        (field (name "Manufacturer Part") "CC0603KRX7R9BB104")
        (field (name "Manufacturer") "YAGEO(国巨)")
      )
      (libsource (lib "easyedapro") (part "CC0603KRX7R9BB104"))
    )
    (comp (ref "C32")
      (value "1uF")
      (footprint "easyedapro:C0603")
      (fields
        (field (name "Manufacturer Part") "CL10A105KB8NNNC")
        (field (name "Manufacturer") "SAMSUNG(三星)")
      )
      (libsource (lib "easyedapro") (part "CL10A105KB8NNNC"))
    )
    (comp (ref "C33")
      (value "100nF")
      (footprint "easyedapro:C0603")
      (description "Capacitance:100nF Tolerance:±10% Tolerance:±10% Voltage Rating:50V Temperature Coefficient:X7R")
      (fields
        (field (name "Manufacturer Part") "CC0603KRX7R9BB104")
        (field (name "Manufacturer") "YAGEO(国巨)")
      )
      (libsource (lib "easyedapro") (part "CC0603KRX7R9BB104"))
    )
    (comp (ref "R33")
      (value "10kΩ")
      (footprint "easyedapro:R0603")
      (fields
        (field (name "Manufacturer Part") "0603WAF1002T5E")
        (field (name "Manufacturer") "UNI-ROYAL(厚声)")
      )
      (libsource (lib "easyedapro") (part "0603WAF1002T5E"))
    )
    (comp (ref "R34")
      (value "10kΩ")
      (footprint "easyedapro:R0603")
      (fields
        (field (name "Manufacturer Part") "0603WAF1002T5E")
        (field (name "Manufacturer") "UNI-ROYAL(厚声)")
      )
      (libsource (lib "easyedapro") (part "0603WAF1002T5E"))
    )
    (comp (ref "R35")
      (value "10kΩ")
      (footprint "easyedapro:R0603")
      (fields
        (field (name "Manufacturer Part") "0603WAF1002T5E")
        (field (name "Manufacturer") "UNI-ROYAL(厚声)")
      )
      (libsource (lib "easyedapro") (part "0603WAF1002T5E"))
    )
    (comp (ref "R36")
      (value "10kΩ")
      (footprint "easyedapro:R0603")
      (fields
        (field (name "Manufacturer Part") "0603WAF1002T5E")
        (field (name "Manufacturer") "UNI-ROYAL(厚声)")
      )
      (libsource (lib "easyedapro") (part "0603WAF1002T5E"))
    )
    (comp (ref "R37")
      (value "0Ω")
      (footprint "easyedapro:R0805")
      (fields
        (field (name "Manufacturer Part") "0805W8F0000T5E")
        (field (name "Manufacturer") "UNI-ROYAL(厚声)")
      )
      (libsource (lib "easyedapro") (part "0805W8F0000T5E"))
    )
    (comp (ref "R38")
      (value "0Ω")
      (footprint "easyedapro:R0805")
      (fields
        (field (name "Manufacturer Part") "0805W8F0000T5E")
        (field (name "Manufacturer") "UNI-ROYAL(厚声)")
      )
      (libsource (lib "easyedapro") (part "0805W8F0000T5E"))
    )
    (comp (ref "U13")
      (value "STM8S003F3P6TR")
      (footprint "easyedapro:TSSOP-20_L6.5-W4.4-P0.65-LS6.4-BL")
      (fields (field (name "Manufacturer") "ST(意法半导体)"))
      (libsource (lib "easyedapro") (part "STM8S003F3P6TR"))
    )
    (comp (ref "U14")
      (value "74HC595D,118")
      (footprint "easyedapro:SOIC-16_L9.9-W3.9-P1.27-LS6.0-BL")
      (fields (field (name "Manufacturer") "Nexperia(安世)"))
      (libsource (lib "easyedapro") (part "74HC595D,118"))
    )
    (comp (ref "LED1")
      (value "TZ-LAMP05RB4HD-C")
      (footprint "easyedapro:LED-TH_3P-BD5.8-P2.54-R-BI")
      (fields (field (name "Manufacturer") "TUOZHAN(拓展光电)"))
      (libsource (lib "easyedapro") (part "TZ-LAMP05RB4HD-C"))
    )
    (comp (ref "LED2")
      (value "TZ-LAMP05RB4HD-C")
      (footprint "easyedapro:LED-TH_3P-BD5.8-P2.54-R-BI")
      (fields (field (name "Manufacturer") "TUOZHAN(拓展光电)"))
      (libsource (lib "easyedapro") (part "TZ-LAMP05RB4HD-C"))
    )
    (comp (ref "LED3")
      (value "TZ-LAMP05RB4HD-C")
      (footprint "easyedapro:LED-TH_3P-BD5.8-P2.54-R-BI")
      (fields (field (name "Manufacturer") "TUOZHAN(拓展光电)"))
      (libsource (lib "easyedapro") (part "TZ-LAMP05RB4HD-C"))
    )
    (comp (ref "LED4")
      (value "TZ-LAMP05RB4HD-C")
      (footprint "easyedapro:LED-TH_3P-BD5.8-P2.54-R-BI")
      (fields (field (name "Manufacturer") "TUOZHAN(拓展光电)"))
      (libsource (lib "easyedapro") (part "TZ-LAMP05RB4HD-C"))
    )
    (comp (ref "R26")
      (value "1kΩ")
      (footprint "easyedapro:R0805")
      (fields
        (field (name "Manufacturer Part") "0805W8F1001T5E")
        (field (name "Manufacturer") "UNI-ROYAL(厚声)")
      )
      (libsource (lib "easyedapro") (part "0805W8F1001T5E"))
    )
    (comp (ref "R27")
      (value "1kΩ")
      (footprint "easyedapro:R0805")
      (fields
        (field (name "Manufacturer Part") "0805W8F1001T5E")
        (field (name "Manufacturer") "UNI-ROYAL(厚声)")
      )
      (libsource (lib "easyedapro") (part "0805W8F1001T5E"))
    )
    (comp (ref "R28")
      (value "1kΩ")
      (footprint "easyedapro:R0805")
      (fields
        (field (name "Manufacturer Part") "0805W8F1001T5E")
        (field (name "Manufacturer") "UNI-ROYAL(厚声)")
      )
      (libsource (lib "easyedapro") (part "0805W8F1001T5E"))
    )
    (comp (ref "R29")
      (value "1kΩ")
      (footprint "easyedapro:R0805")
      (fields
        (field (name "Manufacturer Part") "0805W8F1001T5E")
        (field (name "Manufacturer") "UNI-ROYAL(厚声)")
      )
      (libsource (lib "easyedapro") (part "0805W8F1001T5E"))
    )
  )
  (nets
    (net (code "1") (name "+5V") (class "Default")
      (node (ref "C12") (pin "2") (pinfunction "2_2") (pintype "unspecified"))
      (node (ref "C17") (pin "2") (pinfunction "2_2") (pintype "unspecified"))
      (node (ref "C22") (pin "2") (pinfunction "2_2") (pintype "unspecified"))
      (node (ref "C27") (pin "2") (pinfunction "2_2") (pintype "unspecified"))
      (node (ref "C29") (pin "1") (pinfunction "1_1") (pintype "input"))
      (node (ref "C30") (pin "2") (pinfunction "2_2") (pintype "unspecified"))
      (node (ref "C31") (pin "2") (pinfunction "2_2") (pintype "unspecified"))
      (node (ref "C33") (pin "2") (pinfunction "2_2") (pintype "unspecified"))
      (node (ref "C35") (pin "2") (pinfunction "2_2") (pintype "unspecified"))
      (node (ref "C36") (pin "2") (pinfunction "2_2") (pintype "unspecified"))
      (node (ref "C6") (pin "2") (pinfunction "2_2") (pintype "input"))
      (node (ref "CN1") (pin "13") (pinfunction "13_13") (pintype "unspecified"))
      (node (ref "CN1") (pin "6") (pinfunction "6_6") (pintype "unspecified"))
      (node (ref "D1") (pin "5") (pinfunction "5_5") (pintype "unspecified"))
      (node (ref "D2") (pin "5") (pinfunction "5_5") (pintype "unspecified"))
      (node (ref "D8") (pin "5") (pinfunction "5_5") (pintype "unspecified"))
      (node (ref "R22") (pin "1") (pinfunction "1_1") (pintype "input"))
      (node (ref "R23") (pin "1") (pinfunction "1_1") (pintype "input"))
      (node (ref "R24") (pin "1") (pinfunction "1_1") (pintype "input"))
      (node (ref "R25") (pin "1") (pinfunction "1_1") (pintype "input"))
      (node (ref "R37") (pin "1") (pinfunction "1_1") (pintype "input"))
      (node (ref "U10") (pin "10") (pinfunction "VCC_10") (pintype "unspecified"))
      (node (ref "U12") (pin "10") (pinfunction "VCC_10") (pintype "unspecified"))
      (node (ref "U13") (pin "9") (pinfunction "VDD_9") (pintype "unspecified"))
      (node (ref "U14") (pin "10") (pinfunction "MR#_10") (pintype "unspecified"))
      (node (ref "U14") (pin "16") (pinfunction "VCC_16") (pintype "unspecified"))
      (node (ref "U2") (pin "3") (pinfunction "VDD_3") (pintype "unspecified"))
      (node (ref "U3") (pin "6") (pinfunction "VOUT_6") (pintype "unspecified"))
      (node (ref "U6") (pin "10") (pinfunction "VCC_10") (pintype "unspecified"))
      (node (ref "U8") (pin "10") (pinfunction "VCC_10") (pintype "unspecified"))
    )
    (net (code "2") (name "1.5A-SET") (class "Default")
      (node (ref "R8") (pin "1") (pinfunction "1_1") (pintype "input"))
      (node (ref "R9") (pin "1") (pinfunction "1_1") (pintype "input"))
      (node (ref "U13") (pin "12") (pinfunction "PB4_(T)/I_2_C_SCL_[ADC_ETR]_12") (pintype "unspecified"))
    )
    (net (code "3") (name "3A-SET") (class "Default")
      (node (ref "R10") (pin "1") (pinfunction "1_1") (pintype "input"))
      (node (ref "R11") (pin "1") (pinfunction "1_1") (pintype "input"))
      (node (ref "U13") (pin "11") (pinfunction "PB5_(T)/I_2_C_SDA_[TIM1_BKIN]_11") (pintype "unspecified"))
    )
    (net (code "4") (name "595-CLK") (class "Default")
      (node (ref "U13") (pin "15") (pinfunction "PC5_(HS)/SPI_SCK_[TIM2_CH1]_15") (pintype "unspecified"))
      (node (ref "U14") (pin "12") (pinfunction "STCP_12") (pintype "unspecified"))
    )
    (net (code "5") (name "595-DATA") (class "Default")
      (node (ref "U13") (pin "16") (pinfunction "PC6_(HS)/SPI_MOSI_[TIM1_CH1]_16") (pintype "unspecified"))
      (node (ref "U14") (pin "14") (pinfunction "DS_14") (pintype "unspecified"))
    )
    (net (code "6") (name "595-STORE") (class "Default")
      (node (ref "U13") (pin "17") (pinfunction "PC7_(HS)_/SPI_MISO_[TIM1_CH2]_17") (pintype "unspecified"))
      (node (ref "U14") (pin "11") (pinfunction "SHCP_11") (pintype "unspecified"))
    )
    (net (code "7") (name "ACCESS") (class "Default")
      (node (ref "CN1") (pin "1") (pinfunction "1_1") (pintype "unspecified"))
      (node (ref "D2") (pin "1") (pinfunction "1_1") (pintype "unspecified"))
      (node (ref "R1") (pin "1") (pinfunction "1_1") (pintype "input"))
      (node (ref "R38") (pin "1") (pinfunction "1_1") (pintype "input"))
    )
    (net (code "8") (name "ACCESS-READ") (class "Default")
      (node (ref "R37") (pin "2") (pinfunction "2_2") (pintype "input"))
      (node (ref "R38") (pin "2") (pinfunction "2_2") (pintype "input"))
      (node (ref "U13") (pin "13") (pinfunction "PC3_(HS)/TIM1_CH3_[TLI]_[TIM1_CH1N]_13") (pintype "unspecified"))
    )
    (net (code "9") (name "BUSIO1") (class "Default")
      (node (ref "CN1") (pin "8") (pinfunction "8_8") (pintype "unspecified"))
      (node (ref "D1") (pin "6") (pinfunction "6_6") (pintype "unspecified"))
      (node (ref "R3") (pin "2") (pinfunction "2_2") (pintype "input"))
      (node (ref "R36") (pin "1") (pinfunction "1_1") (pintype "input"))
      (node (ref "U13") (pin "18") (pinfunction "PD1(HS)/SWIM_18") (pintype "unspecified"))
    )
    (net (code "10") (name "BUSIO2") (class "Default")
      (node (ref "CN1") (pin "9") (pinfunction "9_9") (pintype "unspecified"))
      (node (ref "D1") (pin "1") (pinfunction "1_1") (pintype "unspecified"))
      (node (ref "R35") (pin "1") (pinfunction "1_1") (pintype "input"))
      (node (ref "R4") (pin "2") (pinfunction "2_2") (pintype "input"))
      (node (ref "U13") (pin "3") (pinfunction "UART1_RX/AIN6/(HS)_PD6_3") (pintype "unspecified"))
    )
    (net (code "11") (name "BUSIO3") (class "Default")
      (node (ref "CN1") (pin "12") (pinfunction "12_12") (pintype "unspecified"))
      (node (ref "D1") (pin "4") (pinfunction "4_4") (pintype "unspecified"))
      (node (ref "R33") (pin "1") (pinfunction "1_1") (pintype "input"))
      (node (ref "R5") (pin "2") (pinfunction "2_2") (pintype "input"))
      (node (ref "U13") (pin "1") (pinfunction "UART1_CK/TIM2_CH1/BEEP/(HS)PD4_1") (pintype "unspecified"))
    )
    (net (code "12") (name "BUSIO4") (class "Default")
      (node (ref "CN1") (pin "15") (pinfunction "15_15") (pintype "unspecified"))
      (node (ref "D1") (pin "3") (pinfunction "3_3") (pintype "unspecified"))
      (node (ref "R34") (pin "1") (pinfunction "1_1") (pintype "input"))
      (node (ref "R6") (pin "2") (pinfunction "2_2") (pintype "input"))
      (node (ref "U13") (pin "2") (pinfunction "UART1_TX/AIN5/(HS)_PD5_2") (pintype "unspecified"))
    )
    (net (code "13") (name "CC1") (class "Default")
      (node (ref "CN2") (pin "A5") (pinfunction "CC1_A5") (pintype "unspecified"))
      (node (ref "D8") (pin "4") (pinfunction "4_4") (pintype "unspecified"))
      (node (ref "R13") (pin "2") (pinfunction "2_2") (pintype "input"))
      (node (ref "U13") (pin "20") (pinfunction "PD3_(HS)/AIN4/TIM2_CH2/ADC_ETR_20") (pintype "unspecified"))
    )
    (net (code "14") (name "CC2") (class "Default")
      (node (ref "CN2") (pin "B5") (pinfunction "CC2_B5") (pintype "unspecified"))
      (node (ref "D8") (pin "6") (pinfunction "6_6") (pintype "unspecified"))
      (node (ref "R12") (pin "2") (pinfunction "2_2") (pintype "input"))
      (node (ref "U13") (pin "19") (pinfunction "PD2_(HS)/AIN3/[TIM2_CH3]_19") (pintype "unspecified"))
    )
    (net (code "15") (name "D+") (class "Default")
      (node (ref "CN2") (pin "A6") (pinfunction "D+_A6") (pintype "unspecified"))
      (node (ref "CN2") (pin "B6") (pinfunction "D+_B6") (pintype "unspecified"))
      (node (ref "D3") (pin "3") (pinfunction "3_3") (pintype "unspecified"))
      (node (ref "D3") (pin "4") (pinfunction "4_4") (pintype "unspecified"))
      (node (ref "U1") (pin "10") (pinfunction "DP_10") (pintype "input"))
    )
    (net (code "16") (name "D+1") (class "Default")
      (node (ref "CN6") (pin "3") (pinfunction "D+_3") (pintype "input"))
      (node (ref "D4") (pin "3") (pinfunction "3_3") (pintype "unspecified"))
      (node (ref "D4") (pin "4") (pinfunction "4_4") (pintype "unspecified"))
      (node (ref "U6") (pin "2") (pinfunction "HSD1+_2") (pintype "unspecified"))
    )
    (net (code "17") (name "D+2") (class "Default")
      (node (ref "CN3") (pin "3") (pinfunction "D+_3") (pintype "input"))
      (node (ref "D5") (pin "3") (pinfunction "3_3") (pintype "unspecified"))
      (node (ref "D5") (pin "4") (pinfunction "4_4") (pintype "unspecified"))
      (node (ref "U8") (pin "2") (pinfunction "HSD1+_2") (pintype "unspecified"))
    )
    (net (code "18") (name "D+3") (class "Default")
      (node (ref "CN4") (pin "3") (pinfunction "D+_3") (pintype "input"))
      (node (ref "D6") (pin "3") (pinfunction "3_3") (pintype "unspecified"))
      (node (ref "D6") (pin "4") (pinfunction "4_4") (pintype "unspecified"))
      (node (ref "U10") (pin "2") (pinfunction "HSD1+_2") (pintype "unspecified"))
    )
    (net (code "19") (name "D+4") (class "Default")
      (node (ref "CN5") (pin "3") (pinfunction "D+_3") (pintype "input"))
      (node (ref "D7") (pin "3") (pinfunction "3_3") (pintype "unspecified"))
      (node (ref "D7") (pin "4") (pinfunction "4_4") (pintype "unspecified"))
      (node (ref "U12") (pin "2") (pinfunction "HSD1+_2") (pintype "unspecified"))
    )
    (net (code "20") (name "D+HUB1") (class "Default")
      (node (ref "U1") (pin "2") (pinfunction "DP4_2") (pintype "input"))
      (node (ref "U6") (pin "4") (pinfunction "D+_4") (pintype "unspecified"))
    )
    (net (code "21") (name "D+HUB2") (class "Default")
      (node (ref "U1") (pin "4") (pinfunction "DP3_4") (pintype "input"))
      (node (ref "U8") (pin "4") (pinfunction "D+_4") (pintype "unspecified"))
    )
    (net (code "22") (name "D+HUB3") (class "Default")
      (node (ref "U1") (pin "6") (pinfunction "DP2_6") (pintype "input"))
      (node (ref "U10") (pin "4") (pinfunction "D+_4") (pintype "unspecified"))
    )
    (net (code "23") (name "D+HUB4") (class "Default")
      (node (ref "U1") (pin "8") (pinfunction "DP1_8") (pintype "input"))
      (node (ref "U12") (pin "4") (pinfunction "D+_4") (pintype "unspecified"))
    )
    (net (code "24") (name "D-") (class "Default")
      (node (ref "CN2") (pin "A7") (pinfunction "D-_A7") (pintype "unspecified"))
      (node (ref "CN2") (pin "B7") (pinfunction "D-_B7") (pintype "unspecified"))
      (node (ref "D3") (pin "1") (pinfunction "1_1") (pintype "unspecified"))
      (node (ref "D3") (pin "6") (pinfunction "6_6") (pintype "unspecified"))
      (node (ref "U1") (pin "9") (pinfunction "DM_9") (pintype "input"))
    )
    (net (code "25") (name "D-1") (class "Default")
      (node (ref "CN6") (pin "2") (pinfunction "D-_2") (pintype "input"))
      (node (ref "D4") (pin "1") (pinfunction "1_1") (pintype "unspecified"))
      (node (ref "D4") (pin "6") (pinfunction "6_6") (pintype "unspecified"))
      (node (ref "U6") (pin "8") (pinfunction "HSD1-_8") (pintype "unspecified"))
    )
    (net (code "26") (name "D-2") (class "Default")
      (node (ref "CN3") (pin "2") (pinfunction "D-_2") (pintype "input"))
      (node (ref "D5") (pin "1") (pinfunction "1_1") (pintype "unspecified"))
      (node (ref "D5") (pin "6") (pinfunction "6_6") (pintype "unspecified"))
      (node (ref "U8") (pin "8") (pinfunction "HSD1-_8") (pintype "unspecified"))
    )
    (net (code "27") (name "D-3") (class "Default")
      (node (ref "CN4") (pin "2") (pinfunction "D-_2") (pintype "input"))
      (node (ref "D6") (pin "1") (pinfunction "1_1") (pintype "unspecified"))
      (node (ref "D6") (pin "6") (pinfunction "6_6") (pintype "unspecified"))
      (node (ref "U10") (pin "8") (pinfunction "HSD1-_8") (pintype "unspecified"))
    )
    (net (code "28") (name "D-4") (class "Default")
      (node (ref "CN5") (pin "2") (pinfunction "D-_2") (pintype "input"))
      (node (ref "D7") (pin "1") (pinfunction "1_1") (pintype "unspecified"))
      (node (ref "D7") (pin "6") (pinfunction "6_6") (pintype "unspecified"))
      (node (ref "U12") (pin "8") (pinfunction "HSD1-_8") (pintype "unspecified"))
    )
    (net (code "29") (name "D-HUB1") (class "Default")
      (node (ref "U1") (pin "1") (pinfunction "DM4_1") (pintype "input"))
      (node (ref "U6") (pin "6") (pinfunction "D-_6") (pintype "unspecified"))
    )
    (net (code "30") (name "D-HUB2") (class "Default")
      (node (ref "U1") (pin "3") (pinfunction "DM3_3") (pintype "input"))
      (node (ref "U8") (pin "6") (pinfunction "D-_6") (pintype "unspecified"))
    )
    (net (code "31") (name "D-HUB3") (class "Default")
      (node (ref "U1") (pin "5") (pinfunction "DM2_5") (pintype "input"))
      (node (ref "U10") (pin "6") (pinfunction "D-_6") (pintype "unspecified"))
    )
    (net (code "32") (name "D-HUB4") (class "Default")
      (node (ref "U1") (pin "7") (pinfunction "DM1_7") (pintype "input"))
      (node (ref "U12") (pin "6") (pinfunction "D-_6") (pintype "unspecified"))
    )
    (net (code "33") (name "DATA-1") (class "Default")
      (node (ref "R22") (pin "2") (pinfunction "2_2") (pintype "input"))
      (node (ref "U14") (pin "1") (pinfunction "Q1_1") (pintype "unspecified"))
      (node (ref "U6") (pin "9") (pinfunction "OE#_9") (pintype "unspecified"))
    )
    (net (code "34") (name "DATA-2") (class "Default")
      (node (ref "R23") (pin "2") (pinfunction "2_2") (pintype "input"))
      (node (ref "U14") (pin "3") (pinfunction "Q3_3") (pintype "unspecified"))
      (node (ref "U8") (pin "9") (pinfunction "OE#_9") (pintype "unspecified"))
    )
    (net (code "35") (name "DATA-3") (class "Default")
      (node (ref "R24") (pin "2") (pinfunction "2_2") (pintype "input"))
      (node (ref "U10") (pin "9") (pinfunction "OE#_9") (pintype "unspecified"))
      (node (ref "U14") (pin "5") (pinfunction "Q5_5") (pintype "unspecified"))
    )
    (net (code "36") (name "DATA-4") (class "Default")
      (node (ref "R25") (pin "2") (pinfunction "2_2") (pintype "input"))
      (node (ref "U12") (pin "9") (pinfunction "OE#_9") (pintype "unspecified"))
      (node (ref "U14") (pin "7") (pinfunction "Q7_7") (pintype "unspecified"))
    )
    (net (code "37") (name "GND") (class "Default")
      (node (ref "C1") (pin "1") (pinfunction "1_1") (pintype "input"))
      (node (ref "C10") (pin "2") (pinfunction "2_2") (pintype "unspecified"))
      (node (ref "C11") (pin "2") (pinfunction "2_2") (pintype "unspecified"))
      (node (ref "C12") (pin "1") (pinfunction "1_1") (pintype "unspecified"))
      (node (ref "C13") (pin "1") (pinfunction "1_1") (pintype "input"))
      (node (ref "C14") (pin "2") (pinfunction "2_2") (pintype "unspecified"))
      (node (ref "C15") (pin "2") (pinfunction "2_2") (pintype "unspecified"))
      (node (ref "C16") (pin "2") (pinfunction "2_2") (pintype "unspecified"))
      (node (ref "C17") (pin "1") (pinfunction "1_1") (pintype "unspecified"))
      (node (ref "C18") (pin "1") (pinfunction "1_1") (pintype "input"))
      (node (ref "C19") (pin "2") (pinfunction "2_2") (pintype "unspecified"))
      (node (ref "C2") (pin "1") (pinfunction "1_1") (pintype "input"))
      (node (ref "C20") (pin "2") (pinfunction "2_2") (pintype "unspecified"))
      (node (ref "C21") (pin "2") (pinfunction "2_2") (pintype "unspecified"))
      (node (ref "C22") (pin "1") (pinfunction "1_1") (pintype "unspecified"))
      (node (ref "C23") (pin "1") (pinfunction "1_1") (pintype "input"))
      (node (ref "C24") (pin "2") (pinfunction "2_2") (pintype "unspecified"))
      (node (ref "C25") (pin "2") (pinfunction "2_2") (pintype "unspecified"))
      (node (ref "C26") (pin "2") (pinfunction "2_2") (pintype "unspecified"))
      (node (ref "C27") (pin "1") (pinfunction "1_1") (pintype "unspecified"))
      (node (ref "C28") (pin "1") (pinfunction "1_1") (pintype "input"))
      (node (ref "C29") (pin "2") (pinfunction "2_2") (pintype "input"))
      (node (ref "C30") (pin "1") (pinfunction "1_1") (pintype "unspecified"))
      (node (ref "C31") (pin "1") (pinfunction "1_1") (pintype "unspecified"))
      (node (ref "C32") (pin "1") (pinfunction "1_1") (pintype "unspecified"))
      (node (ref "C33") (pin "1") (pinfunction "1_1") (pintype "unspecified"))
      (node (ref "C35") (pin "1") (pinfunction "1_1") (pintype "unspecified"))
      (node (ref "C36") (pin "1") (pinfunction "1_1") (pintype "unspecified"))
      (node (ref "C4") (pin "1") (pinfunction "1_1") (pintype "input"))
      (node (ref "C5") (pin "1") (pinfunction "1_1") (pintype "unspecified"))
      (node (ref "C6") (pin "1") (pinfunction "1_1") (pintype "input"))
      (node (ref "C7") (pin "1") (pinfunction "1_1") (pintype "input"))
      (node (ref "C8") (pin "2") (pinfunction "2_2") (pintype "input"))
      (node (ref "C9") (pin "2") (pinfunction "2_2") (pintype "unspecified"))
      (node (ref "CN1") (pin "10") (pinfunction "10_10") (pintype "unspecified"))
      (node (ref "CN1") (pin "11") (pinfunction "11_11") (pintype "unspecified"))
      (node (ref "CN1") (pin "14") (pinfunction "14_14") (pintype "unspecified"))
      (node (ref "CN1") (pin "3") (pinfunction "3_3") (pintype "unspecified"))
      (node (ref "CN2") (pin "A1") (pinfunction "GND_A1") (pintype "unspecified"))
      (node (ref "CN2") (pin "A12") (pinfunction "GND_A12") (pintype "unspecified"))
      (node (ref "CN2") (pin "B1") (pinfunction "GND_B1") (pintype "unspecified"))
      (node (ref "CN2") (pin "B12") (pinfunction "GND_B12") (pintype "unspecified"))
      (node (ref "CN3") (pin "4") (pinfunction "GND_4") (pintype "input"))
      (node (ref "CN3") (pin "SH1") (pinfunction "SH1_SH1") (pintype "unspecified"))
      (node (ref "CN3") (pin "SH2") (pinfunction "SH2_SH2") (pintype "unspecified"))
      (node (ref "CN4") (pin "4") (pinfunction "GND_4") (pintype "input"))
      (node (ref "CN4") (pin "SH1") (pinfunction "SH1_SH1") (pintype "unspecified"))
      (node (ref "CN4") (pin "SH2") (pinfunction "SH2_SH2") (pintype "unspecified"))
      (node (ref "CN5") (pin "4") (pinfunction "GND_4") (pintype "input"))
      (node (ref "CN5") (pin "SH1") (pinfunction "SH1_SH1") (pintype "unspecified"))
      (node (ref "CN5") (pin "SH2") (pinfunction "SH2_SH2") (pintype "unspecified"))
      (node (ref "CN6") (pin "4") (pinfunction "GND_4") (pintype "input"))
      (node (ref "CN6") (pin "SH1") (pinfunction "SH1_SH1") (pintype "unspecified"))
      (node (ref "CN6") (pin "SH2") (pinfunction "SH2_SH2") (pintype "unspecified"))
      (node (ref "D1") (pin "2") (pinfunction "2_2") (pintype "unspecified"))
      (node (ref "D2") (pin "2") (pinfunction "2_2") (pintype "unspecified"))
      (node (ref "D3") (pin "2") (pinfunction "2_2") (pintype "unspecified"))
      (node (ref "D4") (pin "2") (pinfunction "2_2") (pintype "unspecified"))
      (node (ref "D5") (pin "2") (pinfunction "2_2") (pintype "unspecified"))
      (node (ref "D6") (pin "2") (pinfunction "2_2") (pintype "unspecified"))
      (node (ref "D7") (pin "2") (pinfunction "2_2") (pintype "unspecified"))
      (node (ref "D8") (pin "2") (pinfunction "2_2") (pintype "unspecified"))
      (node (ref "R1") (pin "2") (pinfunction "2_2") (pintype "input"))
      (node (ref "R12") (pin "1") (pinfunction "1_1") (pintype "input"))
      (node (ref "R13") (pin "1") (pinfunction "1_1") (pintype "input"))
      (node (ref "R14") (pin "1") (pinfunction "1_1") (pintype "input"))
      (node (ref "R15") (pin "1") (pinfunction "1_1") (pintype "input"))
      (node (ref "R16") (pin "1") (pinfunction "1_1") (pintype "input"))
      (node (ref "R17") (pin "1") (pinfunction "1_1") (pintype "input"))
      (node (ref "R2") (pin "1") (pinfunction "1_1") (pintype "input"))
      (node (ref "R26") (pin "1") (pinfunction "1_1") (pintype "input"))
      (node (ref "R27") (pin "1") (pinfunction "1_1") (pintype "input"))
      (node (ref "R28") (pin "1") (pinfunction "1_1") (pintype "input"))
      (node (ref "R29") (pin "1") (pinfunction "1_1") (pintype "input"))
      (node (ref "R3") (pin "1") (pinfunction "1_1") (pintype "input"))
      (node (ref "R33") (pin "2") (pinfunction "2_2") (pintype "input"))
      (node (ref "R34") (pin "2") (pinfunction "2_2") (pintype "input"))
      (node (ref "R35") (pin "2") (pinfunction "2_2") (pintype "input"))
      (node (ref "R36") (pin "2") (pinfunction "2_2") (pintype "input"))
      (node (ref "R4") (pin "1") (pinfunction "1_1") (pintype "input"))
      (node (ref "R5") (pin "1") (pinfunction "1_1") (pintype "input"))
      (node (ref "R6") (pin "1") (pinfunction "1_1") (pintype "input"))
      (node (ref "R7") (pin "1") (pinfunction "1_1") (pintype "input"))
      (node (ref "U1") (pin "12") (pinfunction "GND_12") (pintype "input"))
      (node (ref "U10") (pin "1") (pinfunction "Sel_1") (pintype "unspecified"))
      (node (ref "U10") (pin "5") (pinfunction "GND_5") (pintype "unspecified"))
      (node (ref "U11") (pin "2") (pinfunction "GND_2") (pintype "unspecified"))
      (node (ref "U12") (pin "1") (pinfunction "Sel_1") (pintype "unspecified"))
      (node (ref "U12") (pin "5") (pinfunction "GND_5") (pintype "unspecified"))
      (node (ref "U13") (pin "7") (pinfunction "VSS_7") (pintype "unspecified"))
      (node (ref "U14") (pin "13") (pinfunction "OE#_13") (pintype "unspecified"))
      (node (ref "U14") (pin "8") (pinfunction "GND_8") (pintype "unspecified"))
      (node (ref "U2") (pin "5") (pinfunction "GND_5") (pintype "unspecified"))
      (node (ref "U3") (pin "2") (pinfunction "GND_2") (pintype "unspecified"))
      (node (ref "U4") (pin "2") (pinfunction "GND_2") (pintype "unspecified"))
      (node (ref "U4") (pin "4") (pinfunction "EN#_4") (pintype "unspecified"))
      (node (ref "U5") (pin "2") (pinfunction "GND_2") (pintype "unspecified"))
      (node (ref "U6") (pin "1") (pinfunction "Sel_1") (pintype "unspecified"))
      (node (ref "U6") (pin "5") (pinfunction "GND_5") (pintype "unspecified"))
      (node (ref "U7") (pin "2") (pinfunction "GND_2") (pintype "unspecified"))
      (node (ref "U8") (pin "1") (pinfunction "Sel_1") (pintype "unspecified"))
      (node (ref "U8") (pin "5") (pinfunction "GND_5") (pintype "unspecified"))
      (node (ref "U9") (pin "2") (pinfunction "GND_2") (pintype "unspecified"))
      (node (ref "X1") (pin "2") (pinfunction "GND_2") (pintype "input"))
      (node (ref "X1") (pin "4") (pinfunction "GND_4") (pintype "input"))
    )
    (net (code "38") (name "INT-OUT") (class "Default")
      (node (ref "CN1") (pin "7") (pinfunction "7_7") (pintype "unspecified"))
      (node (ref "R39") (pin "2") (pinfunction "2_2") (pintype "input"))
    )
    (net (code "39") (name "INTERRUPT") (class "Default")
      (node (ref "D2") (pin "6") (pinfunction "6_6") (pintype "unspecified"))
      (node (ref "R2") (pin "2") (pinfunction "2_2") (pintype "input"))
      (node (ref "R39") (pin "1") (pinfunction "1_1") (pintype "input"))
      (node (ref "U11") (pin "3") (pinfunction "FLAG#_3") (pintype "unspecified"))
      (node (ref "U4") (pin "3") (pinfunction "FLAG#_3") (pintype "unspecified"))
      (node (ref "U5") (pin "3") (pinfunction "FLAG#_3") (pintype "unspecified"))
      (node (ref "U7") (pin "3") (pinfunction "FLAG#_3") (pintype "unspecified"))
      (node (ref "U9") (pin "3") (pinfunction "FLAG#_3") (pintype "unspecified"))
    )
    (net (code "40") (name "LED1") (class "Default")
      (node (ref "LED1") (pin "1") (pinfunction "+_1") (pintype "unspecified"))
      (node (ref "U13") (pin "14") (pinfunction "PC4_(HS)_/TIM1_CH4/CLK_CCO/AIN2/[TIM1_CH2N]_14") (pintype "unspecified"))
    )
    (net (code "41") (name "LED2") (class "Default")
      (node (ref "LED2") (pin "1") (pinfunction "+_1") (pintype "unspecified"))
      (node (ref "U13") (pin "10") (pinfunction "[SPI_NSS]_TIM2_CH3/(HS)_PA3_10") (pintype "unspecified"))
    )
    (net (code "42") (name "LED3") (class "Default")
      (node (ref "LED3") (pin "1") (pinfunction "+_1") (pintype "unspecified"))
      (node (ref "U13") (pin "5") (pinfunction "OSCIN/PA1_5") (pintype "unspecified"))
    )
    (net (code "43") (name "LED4") (class "Default")
      (node (ref "LED4") (pin "1") (pinfunction "+_1") (pintype "unspecified"))
      (node (ref "U13") (pin "6") (pinfunction "OSCOUT/PA2_6") (pintype "unspecified"))
    )
    (net (code "44") (name "Net-(LED1--)") (class "Default")
      (node (ref "LED1") (pin "2") (pinfunction "-_2") (pintype "unspecified"))
      (node (ref "R29") (pin "2") (pinfunction "2_2") (pintype "input"))
    )
    (net (code "45") (name "Net-(LED2--)") (class "Default")
      (node (ref "LED2") (pin "2") (pinfunction "-_2") (pintype "unspecified"))
      (node (ref "R28") (pin "2") (pinfunction "2_2") (pintype "input"))
    )
    (net (code "46") (name "Net-(LED3--)") (class "Default")
      (node (ref "LED3") (pin "2") (pinfunction "-_2") (pintype "unspecified"))
      (node (ref "R27") (pin "2") (pinfunction "2_2") (pintype "input"))
    )
    (net (code "47") (name "Net-(LED4--)") (class "Default")
      (node (ref "LED4") (pin "2") (pinfunction "-_2") (pintype "unspecified"))
      (node (ref "R26") (pin "2") (pinfunction "2_2") (pintype "input"))
    )
    (net (code "48") (name "Net-(U1-VDD18)") (class "Default")
      (node (ref "C2") (pin "2") (pinfunction "2_2") (pintype "input"))
      (node (ref "U1") (pin "14") (pinfunction "VDD18_14") (pintype "input"))
    )
    (net (code "49") (name "Net-(U1-VDD33)") (class "Default")
      (node (ref "C1") (pin "2") (pinfunction "2_2") (pintype "input"))
      (node (ref "U1") (pin "13") (pinfunction "VDD33_13") (pintype "input"))
    )
    (net (code "50") (name "Net-(U1-XIN)") (class "Default")
      (node (ref "U1") (pin "16") (pinfunction "XIN_16") (pintype "input"))
      (node (ref "X1") (pin "3") (pinfunction "OSC2_3") (pintype "input"))
    )
    (net (code "51") (name "Net-(U1-XOUT)") (class "Default")
      (node (ref "U1") (pin "15") (pinfunction "XOUT_15") (pintype "input"))
      (node (ref "X1") (pin "1") (pinfunction "OSC1_1") (pintype "input"))
    )
    (net (code "52") (name "Net-(U4-ISET)") (class "Default")
      (node (ref "R10") (pin "2") (pinfunction "2_2") (pintype "input"))
      (node (ref "R11") (pin "2") (pinfunction "2_2") (pintype "input"))
      (node (ref "R7") (pin "2") (pinfunction "2_2") (pintype "input"))
      (node (ref "R8") (pin "2") (pinfunction "2_2") (pintype "input"))
      (node (ref "R9") (pin "2") (pinfunction "2_2") (pintype "input"))
      (node (ref "U4") (pin "5") (pinfunction "ISET_5") (pintype "unspecified"))
    )
    (net (code "53") (name "Net-(U5-ISET)") (class "Default")
      (node (ref "R14") (pin "2") (pinfunction "2_2") (pintype "input"))
      (node (ref "U5") (pin "5") (pinfunction "ISET_5") (pintype "unspecified"))
    )
    (net (code "54") (name "Net-(U7-ISET)") (class "Default")
      (node (ref "R15") (pin "2") (pinfunction "2_2") (pintype "input"))
      (node (ref "U7") (pin "5") (pinfunction "ISET_5") (pintype "unspecified"))
    )
    (net (code "55") (name "Net-(U9-ISET)") (class "Default")
      (node (ref "R16") (pin "2") (pinfunction "2_2") (pintype "input"))
      (node (ref "U9") (pin "5") (pinfunction "ISET_5") (pintype "unspecified"))
    )
    (net (code "56") (name "Net-(U11-ISET)") (class "Default")
      (node (ref "R17") (pin "2") (pinfunction "2_2") (pintype "input"))
      (node (ref "U11") (pin "5") (pinfunction "ISET_5") (pintype "unspecified"))
    )
    (net (code "57") (name "Net-(U13-VCAP)") (class "Default")
      (node (ref "C32") (pin "2") (pinfunction "2_2") (pintype "unspecified"))
      (node (ref "U13") (pin "8") (pinfunction "VCAP_8") (pintype "unspecified"))
    )
    (net (code "58") (name "ONEWIRE") (class "Default")
      (node (ref "CN1") (pin "2") (pinfunction "2_2") (pintype "unspecified"))
      (node (ref "D2") (pin "4") (pinfunction "4_4") (pintype "unspecified"))
      (node (ref "U2") (pin "4") (pinfunction "DQ_4") (pintype "unspecified"))
    )
    (net (code "59") (name "POWER-1") (class "Default")
      (node (ref "R21") (pin "2") (pinfunction "2_2") (pintype "input"))
      (node (ref "U14") (pin "15") (pinfunction "Q0_15") (pintype "unspecified"))
      (node (ref "U5") (pin "4") (pinfunction "EN#_4") (pintype "unspecified"))
    )
    (net (code "60") (name "POWER-2") (class "Default")
      (node (ref "R20") (pin "2") (pinfunction "2_2") (pintype "input"))
      (node (ref "U14") (pin "2") (pinfunction "Q2_2") (pintype "unspecified"))
      (node (ref "U7") (pin "4") (pinfunction "EN#_4") (pintype "unspecified"))
    )
    (net (code "61") (name "POWER-3") (class "Default")
      (node (ref "R19") (pin "2") (pinfunction "2_2") (pintype "input"))
      (node (ref "U14") (pin "4") (pinfunction "Q4_4") (pintype "unspecified"))
      (node (ref "U9") (pin "4") (pinfunction "EN#_4") (pintype "unspecified"))
    )
    (net (code "62") (name "POWER-4") (class "Default")
      (node (ref "R18") (pin "2") (pinfunction "2_2") (pintype "input"))
      (node (ref "U11") (pin "4") (pinfunction "EN#_4") (pintype "unspecified"))
      (node (ref "U14") (pin "6") (pinfunction "Q6_6") (pintype "unspecified"))
    )
    (net (code "63") (name "VDS1") (class "Default")
      (node (ref "C10") (pin "1") (pinfunction "1_1") (pintype "unspecified"))
      (node (ref "C11") (pin "1") (pinfunction "1_1") (pintype "unspecified"))
      (node (ref "C9") (pin "1") (pinfunction "1_1") (pintype "unspecified"))
      (node (ref "CN6") (pin "1") (pinfunction "VCC_1") (pintype "input"))
      (node (ref "D4") (pin "5") (pinfunction "5_5") (pintype "unspecified"))
      (node (ref "LED1") (pin "3") (pinfunction "+_3") (pintype "unspecified"))
      (node (ref "U5") (pin "1") (pinfunction "VOUT_1") (pintype "unspecified"))
    )
    (net (code "64") (name "VDS2") (class "Default")
      (node (ref "C14") (pin "1") (pinfunction "1_1") (pintype "unspecified"))
      (node (ref "C15") (pin "1") (pinfunction "1_1") (pintype "unspecified"))
      (node (ref "C16") (pin "1") (pinfunction "1_1") (pintype "unspecified"))
      (node (ref "CN3") (pin "1") (pinfunction "VCC_1") (pintype "input"))
      (node (ref "D5") (pin "5") (pinfunction "5_5") (pintype "unspecified"))
      (node (ref "LED2") (pin "3") (pinfunction "+_3") (pintype "unspecified"))
      (node (ref "U7") (pin "1") (pinfunction "VOUT_1") (pintype "unspecified"))
    )
    (net (code "65") (name "VDS3") (class "Default")
      (node (ref "C19") (pin "1") (pinfunction "1_1") (pintype "unspecified"))
      (node (ref "C20") (pin "1") (pinfunction "1_1") (pintype "unspecified"))
      (node (ref "C21") (pin "1") (pinfunction "1_1") (pintype "unspecified"))
      (node (ref "CN4") (pin "1") (pinfunction "VCC_1") (pintype "input"))
      (node (ref "D6") (pin "5") (pinfunction "5_5") (pintype "unspecified"))
      (node (ref "LED3") (pin "3") (pinfunction "+_3") (pintype "unspecified"))
      (node (ref "U9") (pin "1") (pinfunction "VOUT_1") (pintype "unspecified"))
    )
    (net (code "66") (name "VDS4") (class "Default")
      (node (ref "C24") (pin "1") (pinfunction "1_1") (pintype "unspecified"))
      (node (ref "C25") (pin "1") (pinfunction "1_1") (pintype "unspecified"))
      (node (ref "C26") (pin "1") (pinfunction "1_1") (pintype "unspecified"))
      (node (ref "CN5") (pin "1") (pinfunction "VCC_1") (pintype "input"))
      (node (ref "D7") (pin "5") (pinfunction "5_5") (pintype "unspecified"))
      (node (ref "LED4") (pin "3") (pinfunction "+_3") (pintype "unspecified"))
      (node (ref "U11") (pin "1") (pinfunction "VOUT_1") (pintype "unspecified"))
    )
    (net (code "67") (name "VIN") (class "Default")
      (node (ref "C13") (pin "2") (pinfunction "2_2") (pintype "input"))
      (node (ref "C18") (pin "2") (pinfunction "2_2") (pintype "input"))
      (node (ref "C23") (pin "2") (pinfunction "2_2") (pintype "input"))
      (node (ref "C28") (pin "2") (pinfunction "2_2") (pintype "input"))
      (node (ref "C4") (pin "2") (pinfunction "2_2") (pintype "input"))
      (node (ref "C5") (pin "2") (pinfunction "2_2") (pintype "unspecified"))
      (node (ref "C8") (pin "1") (pinfunction "1_1") (pintype "input"))
      (node (ref "R18") (pin "1") (pinfunction "1_1") (pintype "input"))
      (node (ref "R19") (pin "1") (pinfunction "1_1") (pintype "input"))
      (node (ref "R20") (pin "1") (pinfunction "1_1") (pintype "input"))
      (node (ref "R21") (pin "1") (pinfunction "1_1") (pintype "input"))
      (node (ref "U1") (pin "11") (pinfunction "VDD5_11") (pintype "input"))
      (node (ref "U11") (pin "6") (pinfunction "VIN_6") (pintype "unspecified"))
      (node (ref "U3") (pin "1") (pinfunction "VIN_1") (pintype "unspecified"))
      (node (ref "U3") (pin "3") (pinfunction "ON_3") (pintype "unspecified"))
      (node (ref "U4") (pin "1") (pinfunction "VOUT_1") (pintype "unspecified"))
      (node (ref "U5") (pin "6") (pinfunction "VIN_6") (pintype "unspecified"))
      (node (ref "U7") (pin "6") (pinfunction "VIN_6") (pintype "unspecified"))
      (node (ref "U9") (pin "6") (pinfunction "VIN_6") (pintype "unspecified"))
    )
    (net (code "68") (name "VUSB") (class "Default")
      (node (ref "C7") (pin "2") (pinfunction "2_2") (pintype "input"))
      (node (ref "CN2") (pin "A4") (pinfunction "VBUS_A4") (pintype "unspecified"))
      (node (ref "CN2") (pin "A9") (pinfunction "VBUS_A9") (pintype "unspecified"))
      (node (ref "CN2") (pin "B4") (pinfunction "VBUS_B4") (pintype "unspecified"))
      (node (ref "CN2") (pin "B9") (pinfunction "VBUS_B9") (pintype "unspecified"))
      (node (ref "D3") (pin "5") (pinfunction "5_5") (pintype "unspecified"))
      (node (ref "U4") (pin "6") (pinfunction "VIN_6") (pintype "unspecified"))
    )
    (net (code "69") (name "unconnected-(CN1-Pad4)") (class "Default")
      (node (ref "CN1") (pin "4") (pinfunction "4_4") (pintype "unspecified+no_connect"))
    )
    (net (code "70") (name "unconnected-(CN1-Pad5)") (class "Default")
      (node (ref "CN1") (pin "5") (pinfunction "5_5") (pintype "unspecified+no_connect"))
    )
    (net (code "71") (name "unconnected-(CN1-Pad16)") (class "Default")
      (node (ref "CN1") (pin "16") (pinfunction "16_16") (pintype "unspecified+no_connect"))
    )
    (net (code "72") (name "unconnected-(CN1-Pad17)") (class "Default")
      (node (ref "CN1") (pin "17") (pinfunction "17_17") (pintype "unspecified+no_connect"))
    )
    (net (code "73") (name "unconnected-(CN2-SBU1-PadA8)") (class "Default")
      (node (ref "CN2") (pin "A8") (pinfunction "SBU1_A8") (pintype "unspecified+no_connect"))
    )
    (net (code "74") (name "unconnected-(CN2-SBU2-PadB8)") (class "Default")
      (node (ref "CN2") (pin "B8") (pinfunction "SBU2_B8") (pintype "unspecified+no_connect"))
    )
    (net (code "75") (name "unconnected-(CN2-SHELL-Pad0)") (class "Default")
      (node (ref "CN2") (pin "0") (pinfunction "SHELL_0") (pintype "unspecified+no_connect"))
    )
    (net (code "76") (name "unconnected-(D2-Pad3)") (class "Default")
      (node (ref "D2") (pin "3") (pinfunction "3_3") (pintype "unspecified+no_connect"))
    )
    (net (code "77") (name "unconnected-(D8-Pad1)") (class "Default")
      (node (ref "D8") (pin "1") (pinfunction "1_1") (pintype "unspecified+no_connect"))
    )
    (net (code "78") (name "unconnected-(D8-Pad3)") (class "Default")
      (node (ref "D8") (pin "3") (pinfunction "3_3") (pintype "unspecified+no_connect"))
    )
    (net (code "79") (name "unconnected-(U2-NC-Pad1)") (class "Default")
      (node (ref "U2") (pin "1") (pinfunction "NC_1") (pintype "unspecified+no_connect"))
    )
    (net (code "80") (name "unconnected-(U2-NC-Pad2)") (class "Default")
      (node (ref "U2") (pin "2") (pinfunction "NC_2") (pintype "unspecified+no_connect"))
    )
    (net (code "81") (name "unconnected-(U2-NC-Pad6)") (class "Default")
      (node (ref "U2") (pin "6") (pinfunction "NC_6") (pintype "unspecified+no_connect"))
    )
    (net (code "82") (name "unconnected-(U2-NC-Pad7)") (class "Default")
      (node (ref "U2") (pin "7") (pinfunction "NC_7") (pintype "unspecified+no_connect"))
    )
    (net (code "83") (name "unconnected-(U2-NC-Pad8)") (class "Default")
      (node (ref "U2") (pin "8") (pinfunction "NC_8") (pintype "unspecified+no_connect"))
    )
    (net (code "84") (name "unconnected-(U3-NC-Pad4)") (class "Default")
      (node (ref "U3") (pin "4") (pinfunction "NC_4") (pintype "unspecified+no_connect"))
    )
    (net (code "85") (name "unconnected-(U3-NC-Pad5)") (class "Default")
      (node (ref "U3") (pin "5") (pinfunction "NC_5") (pintype "unspecified+no_connect"))
    )
    (net (code "86") (name "unconnected-(U6-HSD2+-Pad3)") (class "Default")
      (node (ref "U6") (pin "3") (pinfunction "HSD2+_3") (pintype "unspecified+no_connect"))
    )
    (net (code "87") (name "unconnected-(U6-HSD2--Pad7)") (class "Default")
      (node (ref "U6") (pin "7") (pinfunction "HSD2-_7") (pintype "unspecified+no_connect"))
    )
    (net (code "88") (name "unconnected-(U8-HSD2+-Pad3)") (class "Default")
      (node (ref "U8") (pin "3") (pinfunction "HSD2+_3") (pintype "unspecified+no_connect"))
    )
    (net (code "89") (name "unconnected-(U8-HSD2--Pad7)") (class "Default")
      (node (ref "U8") (pin "7") (pinfunction "HSD2-_7") (pintype "unspecified+no_connect"))
    )
    (net (code "90") (name "unconnected-(U10-HSD2+-Pad3)") (class "Default")
      (node (ref "U10") (pin "3") (pinfunction "HSD2+_3") (pintype "unspecified+no_connect"))
    )
    (net (code "91") (name "unconnected-(U10-HSD2--Pad7)") (class "Default")
      (node (ref "U10") (pin "7") (pinfunction "HSD2-_7") (pintype "unspecified+no_connect"))
    )
    (net (code "92") (name "unconnected-(U12-HSD2+-Pad3)") (class "Default")
      (node (ref "U12") (pin "3") (pinfunction "HSD2+_3") (pintype "unspecified+no_connect"))
    )
    (net (code "93") (name "unconnected-(U12-HSD2--Pad7)") (class "Default")
      (node (ref "U12") (pin "7") (pinfunction "HSD2-_7") (pintype "unspecified+no_connect"))
    )
    (net (code "94") (name "unconnected-(U13-NRST-Pad4)") (class "Default")
      (node (ref "U13") (pin "4") (pinfunction "NRST_4") (pintype "unspecified+no_connect"))
    )
    (net (code "95") (name "unconnected-(U14-Q7S-Pad9)") (class "Default")
      (node (ref "U14") (pin "9") (pinfunction "Q7S_9") (pintype "unspecified+no_connect"))
    )
  )
)
